# moire_v2_3.net
KiCad netlist of a schematic drawn in EAGLE
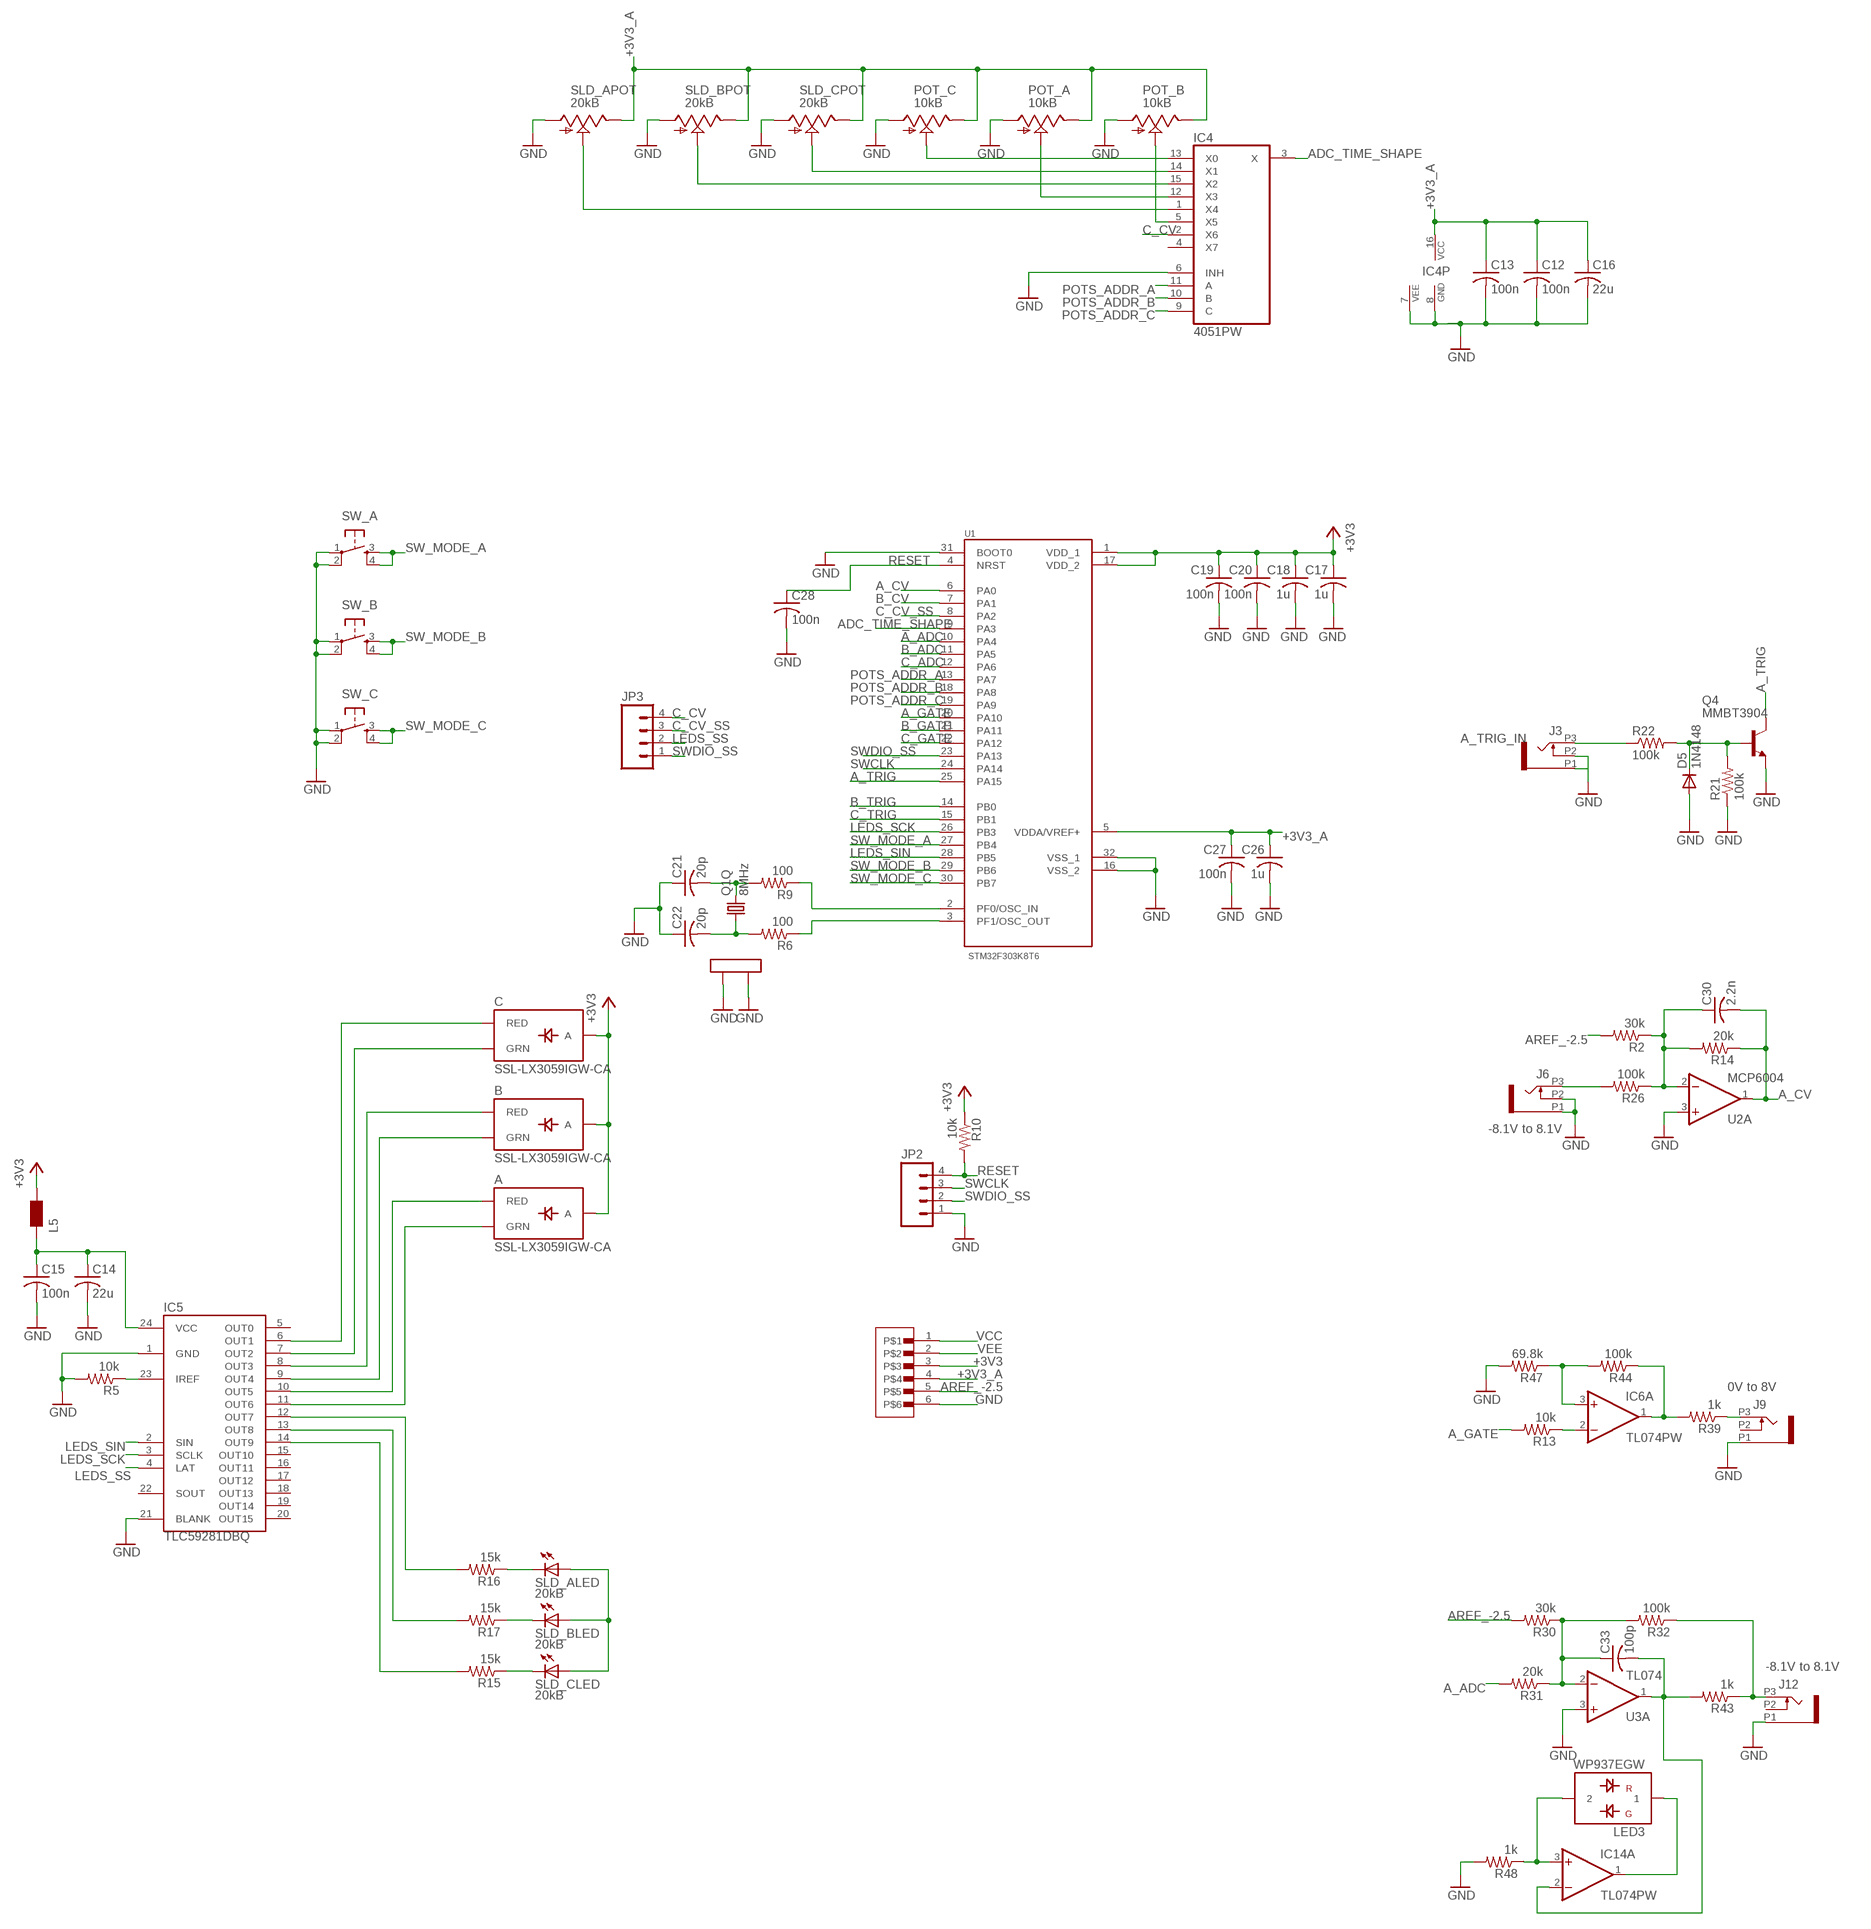
[diagram p0: schematic, sheet 1, part 1 of 2]
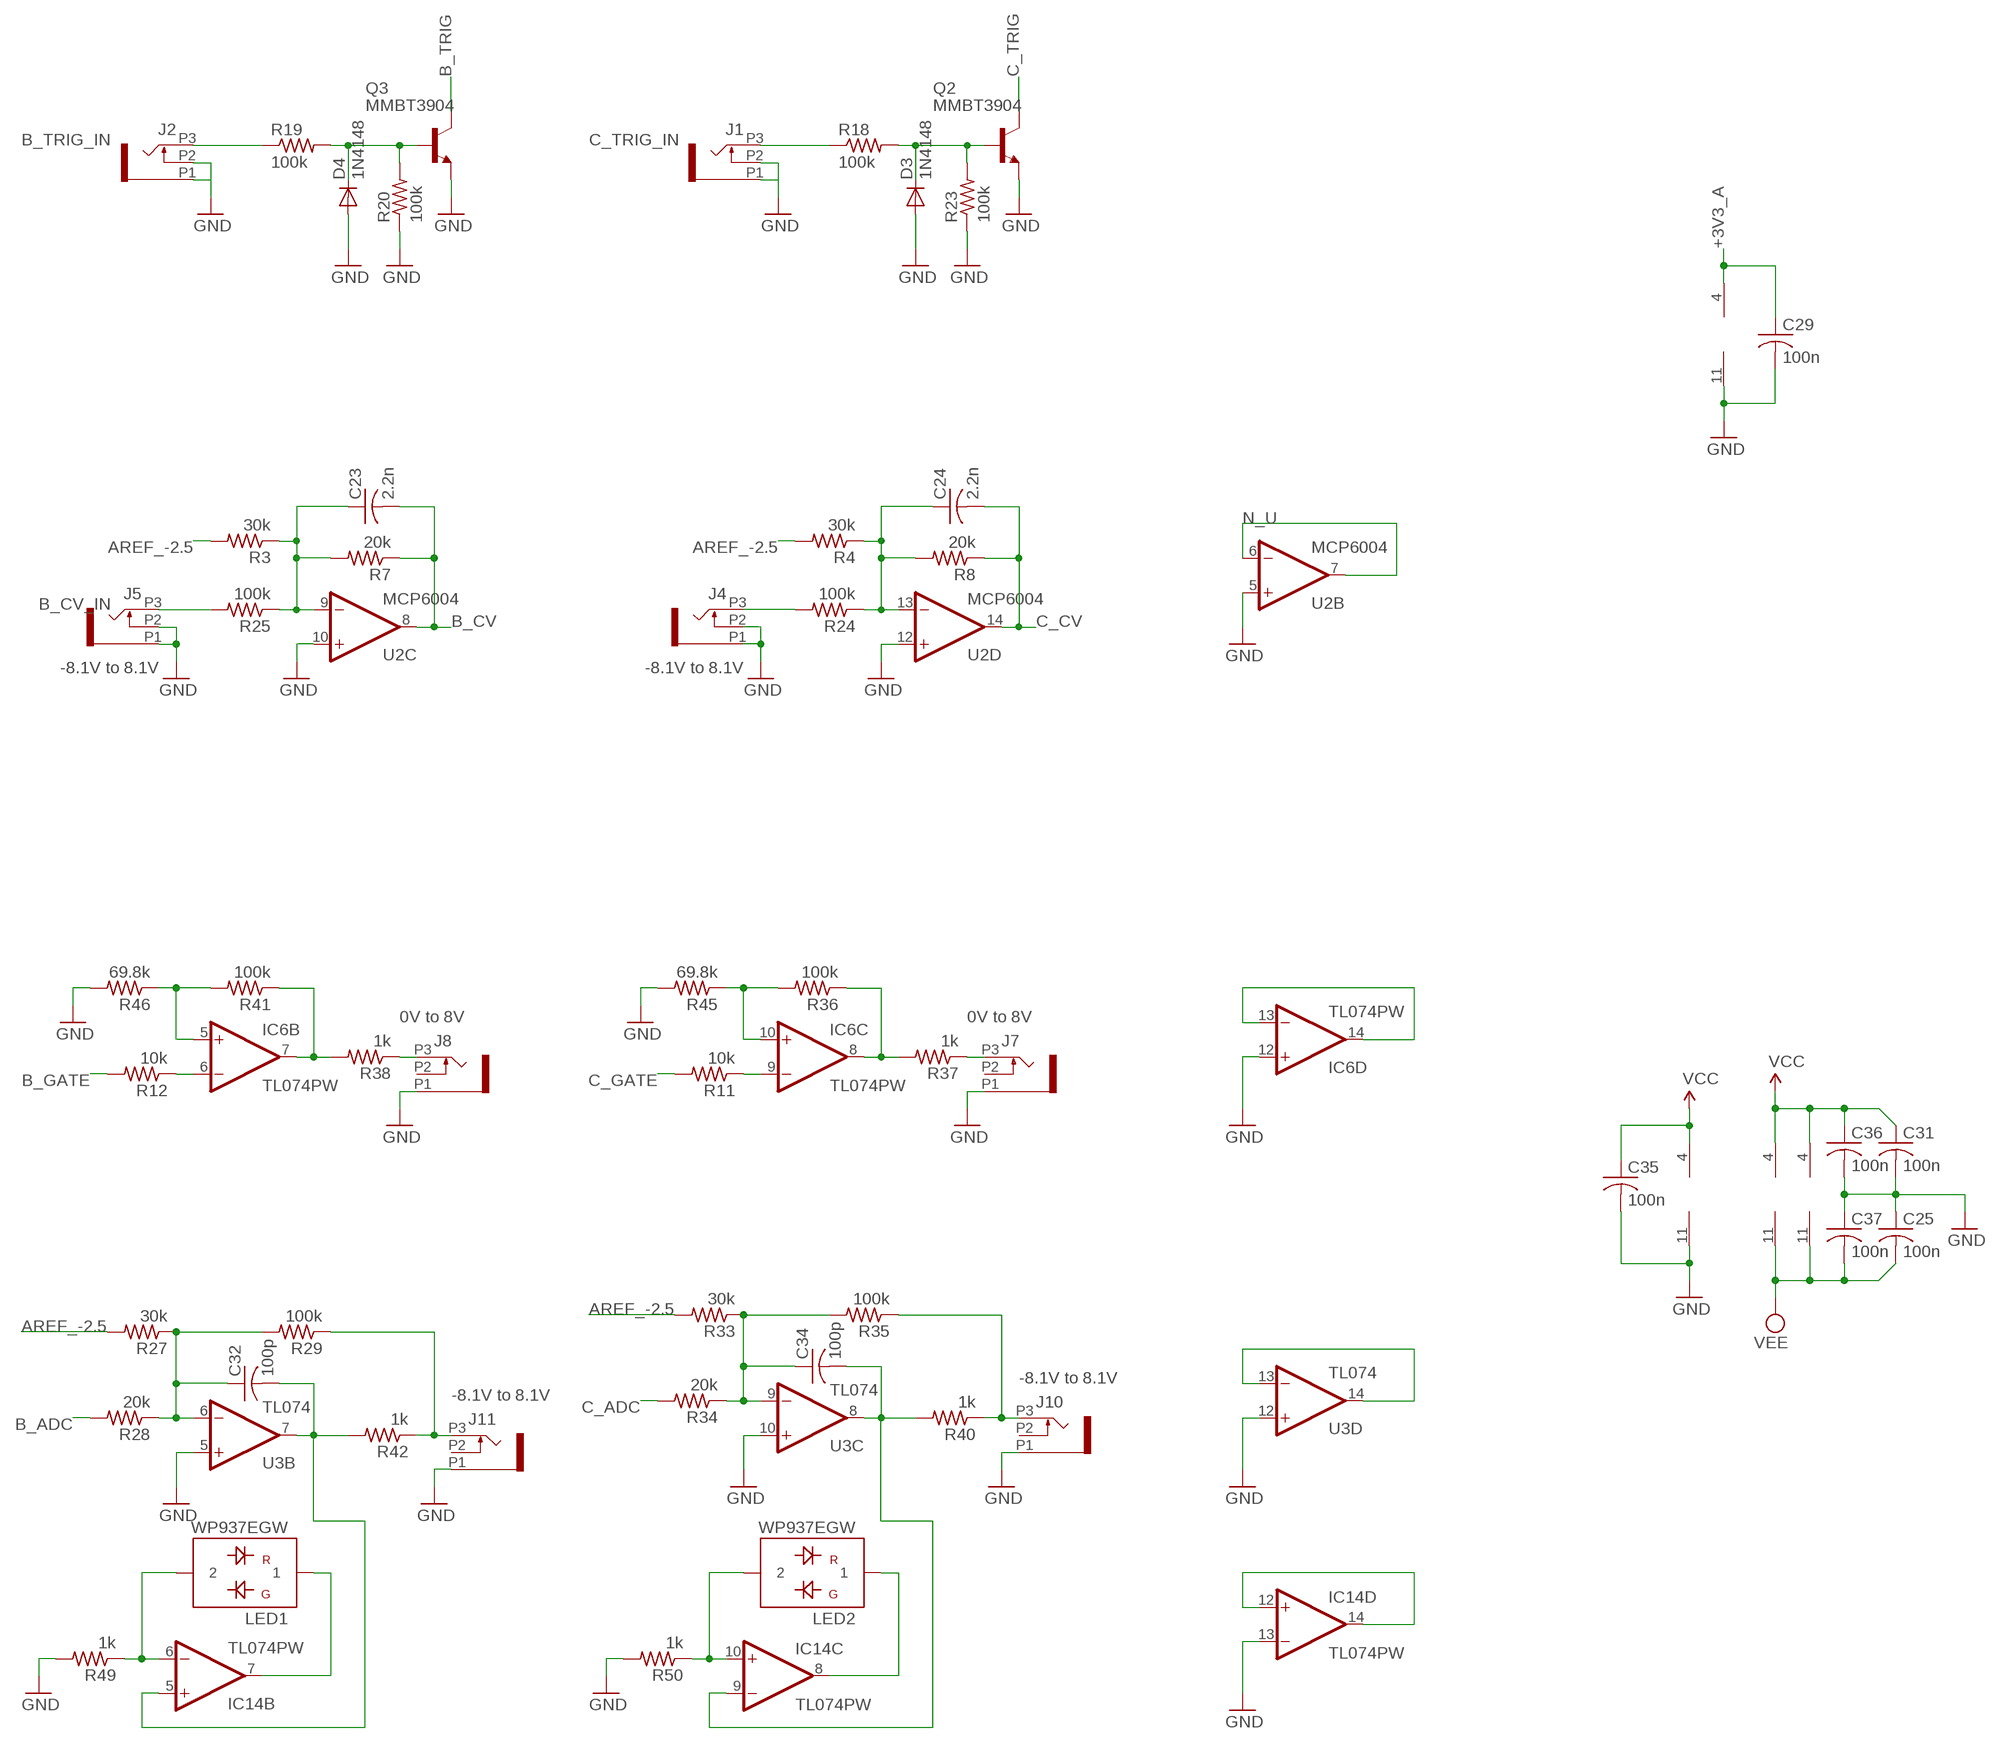
[diagram p1: schematic, sheet 1, part 2 of 2]
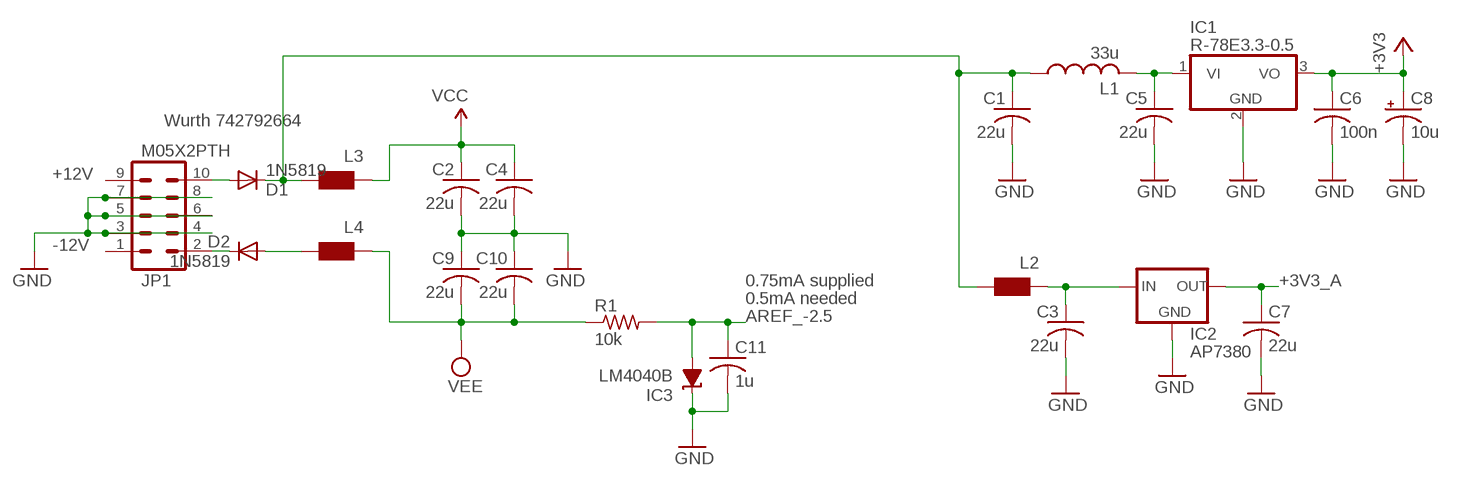
[diagram p2: schematic, sheet 2]

(export (version "E")
  (design (tool "Eeschema 10.0.6"))
  (components
    (comp (ref "A")
      (value "SSL-LX3059IGW-CA")
      (footprint "eagle-import:LED-BICOLOR-THROUGHHOLE-LUMEX")
      (libsource (lib "eagle-import") (part "LED-BICOLOR-THROUGHHOLE-CA"))
    )
    (comp (ref "B")
      (value "SSL-LX3059IGW-CA")
      (footprint "eagle-import:LED-BICOLOR-THROUGHHOLE-LUMEX")
      (libsource (lib "eagle-import") (part "LED-BICOLOR-THROUGHHOLE-CA"))
    )
    (comp (ref "C")
      (value "SSL-LX3059IGW-CA")
      (footprint "eagle-import:LED-BICOLOR-THROUGHHOLE-LUMEX")
      (libsource (lib "eagle-import") (part "LED-BICOLOR-THROUGHHOLE-CA"))
    )
    (comp (ref "C12")
      (value "100n")
      (footprint "eagle-import:RCL_C0603")
      (libsource (lib "eagle-import") (part "RCL_C-USC0603"))
    )
    (comp (ref "C13")
      (value "100n")
      (footprint "eagle-import:RCL_C0603")
      (libsource (lib "eagle-import") (part "RCL_C-USC0603"))
    )
    (comp (ref "C14")
      (value "22u")
      (footprint "eagle-import:RCL_C1206")
      (libsource (lib "eagle-import") (part "RCL_C-USC1206"))
    )
    (comp (ref "C15")
      (value "100n")
      (footprint "eagle-import:RCL_C0603")
      (libsource (lib "eagle-import") (part "RCL_C-USC0603"))
    )
    (comp (ref "C16")
      (value "22u")
      (footprint "eagle-import:RCL_C1206")
      (libsource (lib "eagle-import") (part "RCL_C-USC1206"))
    )
    (comp (ref "C17")
      (value "1u")
      (footprint "eagle-import:RCL_C0603")
      (libsource (lib "eagle-import") (part "RCL_C-USC0603"))
    )
    (comp (ref "C18")
      (value "1u")
      (footprint "eagle-import:RCL_C0603")
      (libsource (lib "eagle-import") (part "RCL_C-USC0603"))
    )
    (comp (ref "C19")
      (value "100n")
      (footprint "eagle-import:RCL_C0603")
      (libsource (lib "eagle-import") (part "RCL_C-USC0603"))
    )
    (comp (ref "C20")
      (value "100n")
      (footprint "eagle-import:RCL_C0603")
      (libsource (lib "eagle-import") (part "RCL_C-USC0603"))
    )
    (comp (ref "C21")
      (value "20p")
      (footprint "eagle-import:RCL_C0603")
      (libsource (lib "eagle-import") (part "RCL_C-USC0603"))
    )
    (comp (ref "C22")
      (value "20p")
      (footprint "eagle-import:RCL_C0603")
      (libsource (lib "eagle-import") (part "RCL_C-USC0603"))
    )
    (comp (ref "C23")
      (value "2.2n")
      (footprint "eagle-import:RCL_C0603")
      (libsource (lib "eagle-import") (part "RCL_C-USC0603"))
    )
    (comp (ref "C24")
      (value "2.2n")
      (footprint "eagle-import:RCL_C0603")
      (libsource (lib "eagle-import") (part "RCL_C-USC0603"))
    )
    (comp (ref "C25")
      (value "100n")
      (footprint "eagle-import:RCL_C0603")
      (libsource (lib "eagle-import") (part "RCL_C-USC0603"))
    )
    (comp (ref "C26")
      (value "1u")
      (footprint "eagle-import:RCL_C0603")
      (libsource (lib "eagle-import") (part "RCL_C-USC0603"))
    )
    (comp (ref "C27")
      (value "100n")
      (footprint "eagle-import:RCL_C0603")
      (libsource (lib "eagle-import") (part "RCL_C-USC0603"))
    )
    (comp (ref "C28")
      (value "100n")
      (footprint "eagle-import:RCL_C0603")
      (libsource (lib "eagle-import") (part "RCL_C-USC0603"))
    )
    (comp (ref "C29")
      (value "100n")
      (footprint "eagle-import:RCL_C0603")
      (libsource (lib "eagle-import") (part "RCL_C-USC0603"))
    )
    (comp (ref "C30")
      (value "2.2n")
      (footprint "eagle-import:RCL_C0603")
      (libsource (lib "eagle-import") (part "RCL_C-USC0603"))
    )
    (comp (ref "C31")
      (value "100n")
      (footprint "eagle-import:RCL_C0603")
      (libsource (lib "eagle-import") (part "RCL_C-USC0603"))
    )
    (comp (ref "C32")
      (value "100p")
      (footprint "eagle-import:RCL_C0603")
      (libsource (lib "eagle-import") (part "RCL_C-USC0603"))
    )
    (comp (ref "C33")
      (value "100p")
      (footprint "eagle-import:RCL_C0603")
      (libsource (lib "eagle-import") (part "RCL_C-USC0603"))
    )
    (comp (ref "C34")
      (value "100p")
      (footprint "eagle-import:RCL_C0603")
      (libsource (lib "eagle-import") (part "RCL_C-USC0603"))
    )
    (comp (ref "C35")
      (value "100n")
      (footprint "eagle-import:RCL_C0603")
      (libsource (lib "eagle-import") (part "RCL_C-USC0603"))
    )
    (comp (ref "C36")
      (value "100n")
      (footprint "eagle-import:RCL_C0603")
      (libsource (lib "eagle-import") (part "RCL_C-USC0603"))
    )
    (comp (ref "C37")
      (value "100n")
      (footprint "eagle-import:RCL_C0603")
      (libsource (lib "eagle-import") (part "RCL_C-USC0603"))
    )
    (comp (ref "D3")
      (value "1N4148")
      (footprint "eagle-import:DIODE_SOD523")
      (libsource (lib "eagle-import") (part "DIODE_DIODE-SOD523"))
    )
    (comp (ref "D4")
      (value "1N4148")
      (footprint "eagle-import:DIODE_SOD523")
      (libsource (lib "eagle-import") (part "DIODE_DIODE-SOD523"))
    )
    (comp (ref "D5")
      (value "1N4148")
      (footprint "eagle-import:DIODE_SOD523")
      (libsource (lib "eagle-import") (part "DIODE_DIODE-SOD523"))
    )
    (comp (ref "IC4")
      (value "4051PW")
      (footprint "eagle-import:TSSOP16_065")
      (libsource (lib "eagle-import") (part "4051PW"))
    )
    (comp (ref "IC5")
      (value "TLC59281DBQ")
      (footprint "eagle-import:TSSOP24_0635")
      (libsource (lib "eagle-import") (part "TLC59281DBQ"))
    )
    (comp (ref "IC6")
      (value "TL074PW")
      (footprint "eagle-import:TSSOP14_065")
      (libsource (lib "eagle-import") (part "og-linear_TL074PW"))
    )
    (comp (ref "IC14")
      (value "TL074PW")
      (footprint "eagle-import:TSSOP14_065")
      (libsource (lib "eagle-import") (part "TL074PW"))
    )
    (comp (ref "J1")
      (value "PJ301_THONKICONN6")
      (footprint "eagle-import:WQP_PJ_301M6")
      (libsource (lib "eagle-import") (part "PJ301_THONKICONN6"))
    )
    (comp (ref "J2")
      (value "PJ301_THONKICONN6")
      (footprint "eagle-import:WQP_PJ_301M6")
      (libsource (lib "eagle-import") (part "PJ301_THONKICONN6"))
    )
    (comp (ref "J3")
      (value "PJ301_THONKICONN6")
      (footprint "eagle-import:WQP_PJ_301M6")
      (libsource (lib "eagle-import") (part "PJ301_THONKICONN6"))
    )
    (comp (ref "J4")
      (value "PJ301_THONKICONN6")
      (footprint "eagle-import:WQP_PJ_301M6")
      (libsource (lib "eagle-import") (part "PJ301_THONKICONN6"))
    )
    (comp (ref "J5")
      (value "PJ301_THONKICONN6")
      (footprint "eagle-import:WQP_PJ_301M6")
      (libsource (lib "eagle-import") (part "PJ301_THONKICONN6"))
    )
    (comp (ref "J6")
      (value "PJ301_THONKICONN6")
      (footprint "eagle-import:WQP_PJ_301M6")
      (libsource (lib "eagle-import") (part "PJ301_THONKICONN6"))
    )
    (comp (ref "J7")
      (value "PJ301_THONKICONN6")
      (footprint "eagle-import:WQP_PJ_301M6")
      (libsource (lib "eagle-import") (part "PJ301_THONKICONN6"))
    )
    (comp (ref "J8")
      (value "PJ301_THONKICONN6")
      (footprint "eagle-import:WQP_PJ_301M6")
      (libsource (lib "eagle-import") (part "PJ301_THONKICONN6"))
    )
    (comp (ref "J9")
      (value "PJ301_THONKICONN6")
      (footprint "eagle-import:WQP_PJ_301M6")
      (libsource (lib "eagle-import") (part "PJ301_THONKICONN6"))
    )
    (comp (ref "J10")
      (value "PJ301_THONKICONN6")
      (footprint "eagle-import:WQP_PJ_301M6")
      (libsource (lib "eagle-import") (part "PJ301_THONKICONN6"))
    )
    (comp (ref "J11")
      (value "PJ301_THONKICONN6")
      (footprint "eagle-import:WQP_PJ_301M6")
      (libsource (lib "eagle-import") (part "PJ301_THONKICONN6"))
    )
    (comp (ref "J12")
      (value "PJ301_THONKICONN6")
      (footprint "eagle-import:WQP_PJ_301M6")
      (libsource (lib "eagle-import") (part "PJ301_THONKICONN6"))
    )
    (comp (ref "JP2")
      (value "M04PTH")
      (footprint "eagle-import:1X04")
      (libsource (lib "eagle-import") (part "M04PTH"))
    )
    (comp (ref "JP3")
      (value "M04PTH")
      (footprint "eagle-import:1X04")
      (libsource (lib "eagle-import") (part "M04PTH"))
    )
    (comp (ref "L5")
      (value "WE-CBF_0603")
      (footprint "eagle-import:0603")
      (libsource (lib "eagle-import") (part "WE-CBF_0603"))
    )
    (comp (ref "LED1")
      (value "WP937EGW")
      (footprint "eagle-import:LED3MM")
      (libsource (lib "eagle-import") (part "LED-BICOLOR-SHARED-THROUGHHOLE"))
    )
    (comp (ref "LED2")
      (value "WP937EGW")
      (footprint "eagle-import:LED3MM")
      (libsource (lib "eagle-import") (part "LED-BICOLOR-SHARED-THROUGHHOLE"))
    )
    (comp (ref "LED3")
      (value "WP937EGW")
      (footprint "eagle-import:LED3MM")
      (libsource (lib "eagle-import") (part "LED-BICOLOR-SHARED-THROUGHHOLE"))
    )
    (comp (ref "POT_A")
      (value "10kB")
      (footprint "eagle-import:ALPS_POT_VERTICAL")
      (libsource (lib "eagle-import") (part "POT_USVERTICAL"))
    )
    (comp (ref "POT_B")
      (value "10kB")
      (footprint "eagle-import:ALPS_POT_VERTICAL")
      (libsource (lib "eagle-import") (part "POT_USVERTICAL"))
    )
    (comp (ref "POT_C")
      (value "10kB")
      (footprint "eagle-import:ALPS_POT_VERTICAL")
      (libsource (lib "eagle-import") (part "POT_USVERTICAL"))
    )
    (comp (ref "Q1")
      (value "8MHz")
      (footprint "eagle-import:CTS406")
      (libsource (lib "eagle-import") (part "CRYSTAL"))
    )
    (comp (ref "Q2")
      (value "MMBT3904")
      (footprint "eagle-import:SOT23-BEC")
      (libsource (lib "eagle-import") (part "-NPN-SOT23-BECMMBT3904LT1"))
    )
    (comp (ref "Q3")
      (value "MMBT3904")
      (footprint "eagle-import:SOT23-BEC")
      (libsource (lib "eagle-import") (part "-NPN-SOT23-BECMMBT3904LT1"))
    )
    (comp (ref "Q4")
      (value "MMBT3904")
      (footprint "eagle-import:SOT23-BEC")
      (libsource (lib "eagle-import") (part "-NPN-SOT23-BECMMBT3904LT1"))
    )
    (comp (ref "R2")
      (value "30k")
      (footprint "eagle-import:RCL_R0603")
      (libsource (lib "eagle-import") (part "RCL_R-US_R0603"))
    )
    (comp (ref "R3")
      (value "30k")
      (footprint "eagle-import:RCL_R0603")
      (libsource (lib "eagle-import") (part "RCL_R-US_R0603"))
    )
    (comp (ref "R4")
      (value "30k")
      (footprint "eagle-import:RCL_R0603")
      (libsource (lib "eagle-import") (part "RCL_R-US_R0603"))
    )
    (comp (ref "R5")
      (value "10k")
      (footprint "eagle-import:RCL_R0603")
      (libsource (lib "eagle-import") (part "RCL_R-US_R0603"))
    )
    (comp (ref "R6")
      (value "100")
      (footprint "eagle-import:RCL_R0603")
      (libsource (lib "eagle-import") (part "RCL_R-US_R0603"))
    )
    (comp (ref "R7")
      (value "20k")
      (footprint "eagle-import:RCL_R0603")
      (libsource (lib "eagle-import") (part "RCL_R-US_R0603"))
    )
    (comp (ref "R8")
      (value "20k")
      (footprint "eagle-import:RCL_R0603")
      (libsource (lib "eagle-import") (part "RCL_R-US_R0603"))
    )
    (comp (ref "R9")
      (value "100")
      (footprint "eagle-import:RCL_R0603")
      (libsource (lib "eagle-import") (part "RCL_R-US_R0603"))
    )
    (comp (ref "R10")
      (value "10k")
      (footprint "eagle-import:RCL_R0603")
      (libsource (lib "eagle-import") (part "RCL_R-US_R0603"))
    )
    (comp (ref "R11")
      (value "10k")
      (footprint "eagle-import:RCL_R0603")
      (libsource (lib "eagle-import") (part "RCL_R-US_R0603"))
    )
    (comp (ref "R12")
      (value "10k")
      (footprint "eagle-import:RCL_R0603")
      (libsource (lib "eagle-import") (part "RCL_R-US_R0603"))
    )
    (comp (ref "R13")
      (value "10k")
      (footprint "eagle-import:RCL_R0603")
      (libsource (lib "eagle-import") (part "RCL_R-US_R0603"))
    )
    (comp (ref "R14")
      (value "20k")
      (footprint "eagle-import:RCL_R0603")
      (libsource (lib "eagle-import") (part "RCL_R-US_R0603"))
    )
    (comp (ref "R15")
      (value "15k")
      (footprint "eagle-import:RCL_R0603")
      (libsource (lib "eagle-import") (part "RCL_R-US_R0603"))
    )
    (comp (ref "R16")
      (value "15k")
      (footprint "eagle-import:RCL_R0603")
      (libsource (lib "eagle-import") (part "RCL_R-US_R0603"))
    )
    (comp (ref "R17")
      (value "15k")
      (footprint "eagle-import:RCL_R0603")
      (libsource (lib "eagle-import") (part "RCL_R-US_R0603"))
    )
    (comp (ref "R18")
      (value "100k")
      (footprint "eagle-import:RCL_R0603")
      (libsource (lib "eagle-import") (part "RCL_R-US_R0603"))
    )
    (comp (ref "R19")
      (value "100k")
      (footprint "eagle-import:RCL_R0603")
      (libsource (lib "eagle-import") (part "RCL_R-US_R0603"))
    )
    (comp (ref "R20")
      (value "100k")
      (footprint "eagle-import:RCL_R0603")
      (libsource (lib "eagle-import") (part "RCL_R-US_R0603"))
    )
    (comp (ref "R21")
      (value "100k")
      (footprint "eagle-import:RCL_R0603")
      (libsource (lib "eagle-import") (part "RCL_R-US_R0603"))
    )
    (comp (ref "R22")
      (value "100k")
      (footprint "eagle-import:RCL_R0603")
      (libsource (lib "eagle-import") (part "RCL_R-US_R0603"))
    )
    (comp (ref "R23")
      (value "100k")
      (footprint "eagle-import:RCL_R0603")
      (libsource (lib "eagle-import") (part "RCL_R-US_R0603"))
    )
    (comp (ref "R24")
      (value "100k")
      (footprint "eagle-import:RCL_R0603")
      (libsource (lib "eagle-import") (part "RCL_R-US_R0603"))
    )
    (comp (ref "R25")
      (value "100k")
      (footprint "eagle-import:RCL_R0603")
      (libsource (lib "eagle-import") (part "RCL_R-US_R0603"))
    )
    (comp (ref "R26")
      (value "100k")
      (footprint "eagle-import:RCL_R0603")
      (libsource (lib "eagle-import") (part "RCL_R-US_R0603"))
    )
    (comp (ref "R27")
      (value "30k")
      (footprint "eagle-import:RCL_R0603")
      (libsource (lib "eagle-import") (part "RCL_R-US_R0603"))
    )
    (comp (ref "R28")
      (value "20k")
      (footprint "eagle-import:RCL_R0603")
      (libsource (lib "eagle-import") (part "RCL_R-US_R0603"))
    )
    (comp (ref "R29")
      (value "100k")
      (footprint "eagle-import:RCL_R0603")
      (libsource (lib "eagle-import") (part "RCL_R-US_R0603"))
    )
    (comp (ref "R30")
      (value "30k")
      (footprint "eagle-import:RCL_R0603")
      (libsource (lib "eagle-import") (part "RCL_R-US_R0603"))
    )
    (comp (ref "R31")
      (value "20k")
      (footprint "eagle-import:RCL_R0603")
      (libsource (lib "eagle-import") (part "RCL_R-US_R0603"))
    )
    (comp (ref "R32")
      (value "100k")
      (footprint "eagle-import:RCL_R0603")
      (libsource (lib "eagle-import") (part "RCL_R-US_R0603"))
    )
    (comp (ref "R33")
      (value "30k")
      (footprint "eagle-import:RCL_R0603")
      (libsource (lib "eagle-import") (part "RCL_R-US_R0603"))
    )
    (comp (ref "R34")
      (value "20k")
      (footprint "eagle-import:RCL_R0603")
      (libsource (lib "eagle-import") (part "RCL_R-US_R0603"))
    )
    (comp (ref "R35")
      (value "100k")
      (footprint "eagle-import:RCL_R0603")
      (libsource (lib "eagle-import") (part "RCL_R-US_R0603"))
    )
    (comp (ref "R36")
      (value "100k")
      (footprint "eagle-import:RCL_R0603")
      (libsource (lib "eagle-import") (part "RCL_R-US_R0603"))
    )
    (comp (ref "R37")
      (value "1k")
      (footprint "eagle-import:RCL_R0603")
      (libsource (lib "eagle-import") (part "RCL_R-US_R0603"))
    )
    (comp (ref "R38")
      (value "1k")
      (footprint "eagle-import:RCL_R0603")
      (libsource (lib "eagle-import") (part "RCL_R-US_R0603"))
    )
    (comp (ref "R39")
      (value "1k")
      (footprint "eagle-import:RCL_R0603")
      (libsource (lib "eagle-import") (part "RCL_R-US_R0603"))
    )
    (comp (ref "R40")
      (value "1k")
      (footprint "eagle-import:RCL_R0603")
      (libsource (lib "eagle-import") (part "RCL_R-US_R0603"))
    )
    (comp (ref "R41")
      (value "100k")
      (footprint "eagle-import:RCL_R0603")
      (libsource (lib "eagle-import") (part "RCL_R-US_R0603"))
    )
    (comp (ref "R42")
      (value "1k")
      (footprint "eagle-import:RCL_R0603")
      (libsource (lib "eagle-import") (part "RCL_R-US_R0603"))
    )
    (comp (ref "R43")
      (value "1k")
      (footprint "eagle-import:RCL_R0603")
      (libsource (lib "eagle-import") (part "RCL_R-US_R0603"))
    )
    (comp (ref "R44")
      (value "100k")
      (footprint "eagle-import:RCL_R0603")
      (libsource (lib "eagle-import") (part "RCL_R-US_R0603"))
    )
    (comp (ref "R45")
      (value "69.8k")
      (footprint "eagle-import:RCL_R0603")
      (libsource (lib "eagle-import") (part "RCL_R-US_R0603"))
    )
    (comp (ref "R46")
      (value "69.8k")
      (footprint "eagle-import:RCL_R0603")
      (libsource (lib "eagle-import") (part "RCL_R-US_R0603"))
    )
    (comp (ref "R47")
      (value "69.8k")
      (footprint "eagle-import:RCL_R0603")
      (libsource (lib "eagle-import") (part "RCL_R-US_R0603"))
    )
    (comp (ref "R48")
      (value "1k")
      (footprint "eagle-import:RCL_R0603")
      (libsource (lib "eagle-import") (part "RCL_R-US_R0603"))
    )
    (comp (ref "R49")
      (value "1k")
      (footprint "eagle-import:RCL_R0603")
      (libsource (lib "eagle-import") (part "RCL_R-US_R0603"))
    )
    (comp (ref "R50")
      (value "1k")
      (footprint "eagle-import:RCL_R0603")
      (libsource (lib "eagle-import") (part "RCL_R-US_R0603"))
    )
    (comp (ref "SLD_A")
      (value "20kB")
      (footprint "eagle-import:BOURNS_SLIDER")
      (libsource (lib "eagle-import") (part "BOURNS_SLIDER"))
    )
    (comp (ref "SLD_B")
      (value "20kB")
      (footprint "eagle-import:BOURNS_SLIDER")
      (libsource (lib "eagle-import") (part "BOURNS_SLIDER"))
    )
    (comp (ref "SLD_C")
      (value "20kB")
      (footprint "eagle-import:BOURNS_SLIDER")
      (libsource (lib "eagle-import") (part "BOURNS_SLIDER"))
    )
    (comp (ref "SW_A")
      (value "TAC_SWITCHPTH")
      (footprint "eagle-import:TACTILE-PTH")
      (libsource (lib "eagle-import") (part "TAC_SWITCHPTH"))
    )
    (comp (ref "SW_B")
      (value "TAC_SWITCHPTH")
      (footprint "eagle-import:TACTILE-PTH")
      (libsource (lib "eagle-import") (part "TAC_SWITCHPTH"))
    )
    (comp (ref "SW_C")
      (value "TAC_SWITCHPTH")
      (footprint "eagle-import:TACTILE-PTH")
      (libsource (lib "eagle-import") (part "TAC_SWITCHPTH"))
    )
    (comp (ref "U$1")
      (value "1X6-SMD-TESTPAD")
      (footprint "eagle-import:6X1-SMD-TESTPAD")
      (libsource (lib "eagle-import") (part "1X6-SMD-TESTPAD"))
    )
    (comp (ref "U1")
      (value "STM32F303K8T6")
      (footprint "eagle-import:QFP80P900X900X160-32N")
      (fields (field (name "MF") "STMicroelectronics"))
      (libsource (lib "eagle-import") (part "STM32F303K8T6"))
    )
    (comp (ref "U2")
      (value "MCP6004")
      (footprint "eagle-import:SO14")
      (libsource (lib "eagle-import") (part "MCP6004_SMD"))
    )
    (comp (ref "U3")
      (value "TL074")
      (footprint "eagle-import:SO14")
      (libsource (lib "eagle-import") (part "TL074_SMD"))
    )
    (comp (ref "C1")
      (value "22u")
      (footprint "eagle-import:RCL_C1206")
      (libsource (lib "eagle-import") (part "RCL_C-USC1206"))
    )
    (comp (ref "C2")
      (value "22u")
      (footprint "eagle-import:RCL_C1206")
      (libsource (lib "eagle-import") (part "RCL_C-USC1206"))
    )
    (comp (ref "C3")
      (value "22u")
      (footprint "eagle-import:RCL_C1206")
      (libsource (lib "eagle-import") (part "RCL_C-USC1206"))
    )
    (comp (ref "C4")
      (value "22u")
      (footprint "eagle-import:RCL_C1206")
      (libsource (lib "eagle-import") (part "RCL_C-USC1206"))
    )
    (comp (ref "C5")
      (value "22u")
      (footprint "eagle-import:RCL_C1206")
      (libsource (lib "eagle-import") (part "RCL_C-USC1206"))
    )
    (comp (ref "C6")
      (value "100n")
      (footprint "eagle-import:RCL_C0603")
      (libsource (lib "eagle-import") (part "RCL_C-USC0603"))
    )
    (comp (ref "C7")
      (value "22u")
      (footprint "eagle-import:RCL_C1206")
      (libsource (lib "eagle-import") (part "RCL_C-USC1206"))
    )
    (comp (ref "C8")
      (value "10u")
      (footprint "eagle-import:RCL_PANASONIC_A")
      (libsource (lib "eagle-import") (part "RCL_CPOL-USA"))
    )
    (comp (ref "C9")
      (value "22u")
      (footprint "eagle-import:RCL_C1206")
      (libsource (lib "eagle-import") (part "RCL_C-USC1206"))
    )
    (comp (ref "C10")
      (value "22u")
      (footprint "eagle-import:RCL_C1206")
      (libsource (lib "eagle-import") (part "RCL_C-USC1206"))
    )
    (comp (ref "C11")
      (value "1u")
      (footprint "eagle-import:RCL_C0603")
      (libsource (lib "eagle-import") (part "RCL_C-USC0603"))
    )
    (comp (ref "D1")
      (value "1N5819")
      (footprint "eagle-import:DIODE_SOD123")
      (libsource (lib "eagle-import") (part "DIODE_DIODE-SOD123"))
    )
    (comp (ref "D2")
      (value "1N5819")
      (footprint "eagle-import:DIODE_SOD123")
      (libsource (lib "eagle-import") (part "DIODE_DIODE-SOD123"))
    )
    (comp (ref "IC1")
      (value "R-78E3.3-0.5")
      (footprint "eagle-import:WE78")
      (libsource (lib "eagle-import") (part "WE173950378"))
    )
    (comp (ref "IC2")
      (value "AP7380")
      (footprint "eagle-import:SOT89")
      (libsource (lib "eagle-import") (part "AP7380"))
    )
    (comp (ref "IC3")
      (value "LM4040B")
      (footprint "eagle-import:DBZ_R-PDSO-G3")
      (libsource (lib "eagle-import") (part "LM4041DBZB12"))
    )
    (comp (ref "JP1")
      (value "M05X2PTH")
      (footprint "eagle-import:2X5-PTH")
      (libsource (lib "eagle-import") (part "M05X2PTH"))
    )
    (comp (ref "L1")
      (value "33u")
      (footprint "eagle-import:L2012C")
      (libsource (lib "eagle-import") (part "L-USL2012C"))
    )
    (comp (ref "L2")
      (value "WE-CBF_0603")
      (footprint "eagle-import:0603")
      (libsource (lib "eagle-import") (part "WE-CBF_0603"))
    )
    (comp (ref "L3")
      (value "WE-CBF_0603")
      (footprint "eagle-import:0603")
      (libsource (lib "eagle-import") (part "WE-CBF_0603"))
    )
    (comp (ref "L4")
      (value "WE-CBF_0603")
      (footprint "eagle-import:0603")
      (libsource (lib "eagle-import") (part "WE-CBF_0603"))
    )
    (comp (ref "R1")
      (value "10k")
      (footprint "eagle-import:RCL_R0603")
      (libsource (lib "eagle-import") (part "RCL_R-US_R0603"))
    )
  )
  (nets
    (net (code "1") (name "+3V3") (class "Default")
      (node (ref "A") (pin "A") (pinfunction "A_A") (pintype "bidirectional"))
      (node (ref "B") (pin "A") (pinfunction "A_A") (pintype "bidirectional"))
      (node (ref "C") (pin "A") (pinfunction "A_A") (pintype "bidirectional"))
      (node (ref "C17") (pin "1") (pinfunction "1_1") (pintype "passive"))
      (node (ref "C18") (pin "1") (pinfunction "1_1") (pintype "passive"))
      (node (ref "C19") (pin "1") (pinfunction "1_1") (pintype "passive"))
      (node (ref "C20") (pin "1") (pinfunction "1_1") (pintype "passive"))
      (node (ref "C6") (pin "1") (pinfunction "1_1") (pintype "passive"))
      (node (ref "C8") (pin "+") (pinfunction "+_+") (pintype "passive"))
      (node (ref "IC1") (pin "3") (pinfunction "VO_3") (pintype "passive"))
      (node (ref "L5") (pin "2") (pinfunction "2_2") (pintype "passive"))
      (node (ref "R10") (pin "1") (pinfunction "1_1") (pintype "passive"))
      (node (ref "U$1") (pin "3") (pinfunction "P$3_3") (pintype "bidirectional"))
      (node (ref "U1") (pin "1") (pinfunction "VDD_1_1") (pintype "power_in"))
      (node (ref "U1") (pin "17") (pinfunction "VDD_2_17") (pintype "power_in"))
    )
    (net (code "2") (name "+3V3_A") (class "Default")
      (node (ref "C12") (pin "1") (pinfunction "1_1") (pintype "passive"))
      (node (ref "C13") (pin "1") (pinfunction "1_1") (pintype "passive"))
      (node (ref "C16") (pin "1") (pinfunction "1_1") (pintype "passive"))
      (node (ref "C26") (pin "1") (pinfunction "1_1") (pintype "passive"))
      (node (ref "C27") (pin "1") (pinfunction "1_1") (pintype "passive"))
      (node (ref "C29") (pin "1") (pinfunction "1_1") (pintype "passive"))
      (node (ref "C7") (pin "1") (pinfunction "1_1") (pintype "passive"))
      (node (ref "IC2") (pin "3") (pinfunction "OUT_3") (pintype "passive"))
      (node (ref "IC4") (pin "16") (pinfunction "VCC_16") (pintype "power_in"))
      (node (ref "POT_A") (pin "P$1") (pinfunction "E_P$1") (pintype "passive"))
      (node (ref "POT_B") (pin "P$1") (pinfunction "E_P$1") (pintype "passive"))
      (node (ref "POT_C") (pin "P$1") (pinfunction "E_P$1") (pintype "passive"))
      (node (ref "SLD_A") (pin "3") (pinfunction "E_3") (pintype "passive"))
      (node (ref "SLD_B") (pin "3") (pinfunction "E_3") (pintype "passive"))
      (node (ref "SLD_C") (pin "3") (pinfunction "E_3") (pintype "passive"))
      (node (ref "U$1") (pin "4") (pinfunction "P$4_4") (pintype "bidirectional"))
      (node (ref "U1") (pin "5") (pinfunction "VDDA/VREF+_5") (pintype "power_in"))
      (node (ref "U2") (pin "4") (pinfunction "V+_4") (pintype "power_in"))
    )
    (net (code "3") (name "+12V") (class "Default")
      (node (ref "D1") (pin "A") (pinfunction "A_A") (pintype "passive"))
      (node (ref "JP1") (pin "10") (pinfunction "10_10") (pintype "passive"))
      (node (ref "JP1") (pin "9") (pinfunction "9_9") (pintype "passive"))
    )
    (net (code "4") (name "-12V") (class "Default")
      (node (ref "D2") (pin "C") (pinfunction "C_C") (pintype "passive"))
      (node (ref "JP1") (pin "1") (pinfunction "1_1") (pintype "passive"))
      (node (ref "JP1") (pin "2") (pinfunction "2_2") (pintype "passive"))
    )
    (net (code "5") (name "ADC_TIME_SHAPE") (class "Default")
      (node (ref "IC4") (pin "3") (pinfunction "X_3") (pintype "bidirectional"))
      (node (ref "U1") (pin "9") (pinfunction "PA3_9") (pintype "bidirectional"))
    )
    (net (code "6") (name "AREF_-2.5") (class "Default")
      (node (ref "C11") (pin "1") (pinfunction "1_1") (pintype "passive"))
      (node (ref "IC3") (pin "2") (pinfunction "A_2") (pintype "passive"))
      (node (ref "R1") (pin "2") (pinfunction "2_2") (pintype "passive"))
      (node (ref "R2") (pin "2") (pinfunction "2_2") (pintype "passive"))
      (node (ref "R27") (pin "2") (pinfunction "2_2") (pintype "passive"))
      (node (ref "R3") (pin "2") (pinfunction "2_2") (pintype "passive"))
      (node (ref "R30") (pin "2") (pinfunction "2_2") (pintype "passive"))
      (node (ref "R33") (pin "2") (pinfunction "2_2") (pintype "passive"))
      (node (ref "R4") (pin "2") (pinfunction "2_2") (pintype "passive"))
      (node (ref "U$1") (pin "5") (pinfunction "P$5_5") (pintype "bidirectional"))
    )
    (net (code "7") (name "A_ADC") (class "Default")
      (node (ref "R31") (pin "2") (pinfunction "2_2") (pintype "passive"))
      (node (ref "U1") (pin "10") (pinfunction "PA4_10") (pintype "bidirectional"))
    )
    (net (code "8") (name "A_CV") (class "Default")
      (node (ref "C30") (pin "2") (pinfunction "2_2") (pintype "passive"))
      (node (ref "R14") (pin "1") (pinfunction "1_1") (pintype "passive"))
      (node (ref "U1") (pin "6") (pinfunction "PA0_6") (pintype "bidirectional"))
      (node (ref "U2") (pin "1") (pinfunction "OUT_1") (pintype "output"))
    )
    (net (code "9") (name "A_GATE") (class "Default")
      (node (ref "R13") (pin "2") (pinfunction "2_2") (pintype "passive"))
      (node (ref "U1") (pin "20") (pinfunction "PA10_20") (pintype "bidirectional"))
    )
    (net (code "10") (name "A_TRIG") (class "Default")
      (node (ref "Q4") (pin "C") (pinfunction "C_C") (pintype "passive"))
      (node (ref "U1") (pin "25") (pinfunction "PA15_25") (pintype "bidirectional"))
    )
    (net (code "11") (name "A_TRIG_IN") (class "Default")
      (node (ref "J3") (pin "P3") (pinfunction "3_P3") (pintype "passive"))
      (node (ref "R22") (pin "1") (pinfunction "1_1") (pintype "passive"))
    )
    (net (code "12") (name "B_ADC") (class "Default")
      (node (ref "R28") (pin "2") (pinfunction "2_2") (pintype "passive"))
      (node (ref "U1") (pin "11") (pinfunction "PA5_11") (pintype "bidirectional"))
    )
    (net (code "13") (name "B_CV") (class "Default")
      (node (ref "C23") (pin "2") (pinfunction "2_2") (pintype "passive"))
      (node (ref "R7") (pin "1") (pinfunction "1_1") (pintype "passive"))
      (node (ref "U1") (pin "7") (pinfunction "PA1_7") (pintype "bidirectional"))
      (node (ref "U2") (pin "8") (pinfunction "OUT_8") (pintype "output"))
    )
    (net (code "14") (name "B_CV_IN") (class "Default")
      (node (ref "J5") (pin "P3") (pinfunction "3_P3") (pintype "passive"))
      (node (ref "R25") (pin "2") (pinfunction "2_2") (pintype "passive"))
    )
    (net (code "15") (name "B_GATE") (class "Default")
      (node (ref "R12") (pin "2") (pinfunction "2_2") (pintype "passive"))
      (node (ref "U1") (pin "21") (pinfunction "PA11_21") (pintype "bidirectional"))
    )
    (net (code "16") (name "B_TRIG") (class "Default")
      (node (ref "Q3") (pin "C") (pinfunction "C_C") (pintype "passive"))
      (node (ref "U1") (pin "14") (pinfunction "PB0_14") (pintype "bidirectional"))
    )
    (net (code "17") (name "B_TRIG_IN") (class "Default")
      (node (ref "J2") (pin "P3") (pinfunction "3_P3") (pintype "passive"))
      (node (ref "R19") (pin "1") (pinfunction "1_1") (pintype "passive"))
    )
    (net (code "18") (name "C_ADC") (class "Default")
      (node (ref "R34") (pin "2") (pinfunction "2_2") (pintype "passive"))
      (node (ref "U1") (pin "12") (pinfunction "PA6_12") (pintype "bidirectional"))
    )
    (net (code "19") (name "C_CV") (class "Default")
      (node (ref "C24") (pin "2") (pinfunction "2_2") (pintype "passive"))
      (node (ref "IC4") (pin "2") (pinfunction "X6_2") (pintype "bidirectional"))
      (node (ref "JP3") (pin "4") (pinfunction "4_4") (pintype "passive"))
      (node (ref "R8") (pin "1") (pinfunction "1_1") (pintype "passive"))
      (node (ref "U2") (pin "14") (pinfunction "OUT_14") (pintype "output"))
    )
    (net (code "20") (name "C_CV_SS") (class "Default")
      (node (ref "JP3") (pin "3") (pinfunction "3_3") (pintype "passive"))
      (node (ref "U1") (pin "8") (pinfunction "PA2_8") (pintype "bidirectional"))
    )
    (net (code "21") (name "C_GATE") (class "Default")
      (node (ref "R11") (pin "2") (pinfunction "2_2") (pintype "passive"))
      (node (ref "U1") (pin "22") (pinfunction "PA12_22") (pintype "bidirectional"))
    )
    (net (code "22") (name "C_TRIG") (class "Default")
      (node (ref "Q2") (pin "C") (pinfunction "C_C") (pintype "passive"))
      (node (ref "U1") (pin "15") (pinfunction "PB1_15") (pintype "bidirectional"))
    )
    (net (code "23") (name "C_TRIG_IN") (class "Default")
      (node (ref "J1") (pin "P3") (pinfunction "3_P3") (pintype "passive"))
      (node (ref "R18") (pin "1") (pinfunction "1_1") (pintype "passive"))
    )
    (net (code "24") (name "GND") (class "Default")
      (node (ref "C1") (pin "2") (pinfunction "2_2") (pintype "passive"))
      (node (ref "C10") (pin "1") (pinfunction "1_1") (pintype "passive"))
      (node (ref "C11") (pin "2") (pinfunction "2_2") (pintype "passive"))
      (node (ref "C12") (pin "2") (pinfunction "2_2") (pintype "passive"))
      (node (ref "C13") (pin "2") (pinfunction "2_2") (pintype "passive"))
      (node (ref "C14") (pin "2") (pinfunction "2_2") (pintype "passive"))
      (node (ref "C15") (pin "2") (pinfunction "2_2") (pintype "passive"))
      (node (ref "C16") (pin "2") (pinfunction "2_2") (pintype "passive"))
      (node (ref "C17") (pin "2") (pinfunction "2_2") (pintype "passive"))
      (node (ref "C18") (pin "2") (pinfunction "2_2") (pintype "passive"))
      (node (ref "C19") (pin "2") (pinfunction "2_2") (pintype "passive"))
      (node (ref "C2") (pin "2") (pinfunction "2_2") (pintype "passive"))
      (node (ref "C20") (pin "2") (pinfunction "2_2") (pintype "passive"))
      (node (ref "C21") (pin "1") (pinfunction "1_1") (pintype "passive"))
      (node (ref "C22") (pin "1") (pinfunction "1_1") (pintype "passive"))
      (node (ref "C25") (pin "1") (pinfunction "1_1") (pintype "passive"))
      (node (ref "C26") (pin "2") (pinfunction "2_2") (pintype "passive"))
      (node (ref "C27") (pin "2") (pinfunction "2_2") (pintype "passive"))
      (node (ref "C28") (pin "2") (pinfunction "2_2") (pintype "passive"))
      (node (ref "C29") (pin "2") (pinfunction "2_2") (pintype "passive"))
      (node (ref "C3") (pin "2") (pinfunction "2_2") (pintype "passive"))
      (node (ref "C31") (pin "2") (pinfunction "2_2") (pintype "passive"))
      (node (ref "C35") (pin "2") (pinfunction "2_2") (pintype "passive"))
      (node (ref "C36") (pin "2") (pinfunction "2_2") (pintype "passive"))
      (node (ref "C37") (pin "1") (pinfunction "1_1") (pintype "passive"))
      (node (ref "C4") (pin "2") (pinfunction "2_2") (pintype "passive"))
      (node (ref "C5") (pin "2") (pinfunction "2_2") (pintype "passive"))
      (node (ref "C6") (pin "2") (pinfunction "2_2") (pintype "passive"))
      (node (ref "C7") (pin "2") (pinfunction "2_2") (pintype "passive"))
      (node (ref "C8") (pin "-") (pinfunction "-_-") (pintype "passive"))
      (node (ref "C9") (pin "1") (pinfunction "1_1") (pintype "passive"))
      (node (ref "D3") (pin "A") (pinfunction "A_A") (pintype "passive"))
      (node (ref "D4") (pin "A") (pinfunction "A_A") (pintype "passive"))
      (node (ref "D5") (pin "A") (pinfunction "A_A") (pintype "passive"))
      (node (ref "IC1") (pin "2") (pinfunction "GND_2") (pintype "passive"))
      (node (ref "IC14") (pin "13") (pinfunction "-IN_13") (pintype "input"))
      (node (ref "IC2") (pin "1") (pinfunction "GND_1") (pintype "input"))
      (node (ref "IC3") (pin "1") (pinfunction "C_1") (pintype "passive"))
      (node (ref "IC4") (pin "6") (pinfunction "INH_6") (pintype "input"))
      (node (ref "IC4") (pin "7") (pinfunction "VEE_7") (pintype "power_in"))
      (node (ref "IC4") (pin "8") (pinfunction "GND_8") (pintype "power_in"))
      (node (ref "IC5") (pin "1") (pinfunction "GND_1") (pintype "bidirectional"))
      (node (ref "IC5") (pin "21") (pinfunction "BLANK_21") (pintype "bidirectional"))
      (node (ref "IC6") (pin "11") (pinfunction "V-_11") (pintype "power_in"))
      (node (ref "IC6") (pin "12") (pinfunction "+IN_12") (pintype "input"))
      (node (ref "J1") (pin "P1") (pinfunction "1_P1") (pintype "passive"))
      (node (ref "J1") (pin "P2") (pinfunction "2_P2") (pintype "passive"))
      (node (ref "J10") (pin "P1") (pinfunction "1_P1") (pintype "passive"))
      (node (ref "J11") (pin "P1") (pinfunction "1_P1") (pintype "passive"))
      (node (ref "J12") (pin "P1") (pinfunction "1_P1") (pintype "passive"))
      (node (ref "J2") (pin "P1") (pinfunction "1_P1") (pintype "passive"))
      (node (ref "J2") (pin "P2") (pinfunction "2_P2") (pintype "passive"))
      (node (ref "J3") (pin "P1") (pinfunction "1_P1") (pintype "passive"))
      (node (ref "J3") (pin "P2") (pinfunction "2_P2") (pintype "passive"))
      (node (ref "J4") (pin "P1") (pinfunction "1_P1") (pintype "passive"))
      (node (ref "J4") (pin "P2") (pinfunction "2_P2") (pintype "passive"))
      (node (ref "J5") (pin "P1") (pinfunction "1_P1") (pintype "passive"))
      (node (ref "J5") (pin "P2") (pinfunction "2_P2") (pintype "passive"))
      (node (ref "J6") (pin "P1") (pinfunction "1_P1") (pintype "passive"))
      (node (ref "J6") (pin "P2") (pinfunction "2_P2") (pintype "passive"))
      (node (ref "J7") (pin "P1") (pinfunction "1_P1") (pintype "passive"))
      (node (ref "J8") (pin "P1") (pinfunction "1_P1") (pintype "passive"))
      (node (ref "J9") (pin "P1") (pinfunction "1_P1") (pintype "passive"))
      (node (ref "JP1") (pin "3") (pinfunction "3_3") (pintype "passive"))
      (node (ref "JP1") (pin "4") (pinfunction "4_4") (pintype "passive"))
      (node (ref "JP1") (pin "5") (pinfunction "5_5") (pintype "passive"))
      (node (ref "JP1") (pin "6") (pinfunction "6_6") (pintype "passive"))
      (node (ref "JP1") (pin "7") (pinfunction "7_7") (pintype "passive"))
      (node (ref "JP1") (pin "8") (pinfunction "8_8") (pintype "passive"))
      (node (ref "JP2") (pin "1") (pinfunction "1_1") (pintype "passive"))
      (node (ref "POT_A") (pin "P$3") (pinfunction "A_P$3") (pintype "passive"))
      (node (ref "POT_B") (pin "P$3") (pinfunction "A_P$3") (pintype "passive"))
      (node (ref "POT_C") (pin "P$3") (pinfunction "A_P$3") (pintype "passive"))
      (node (ref "Q1") (pin "2") (pinfunction "LID1_2") (pintype "power_in"))
      (node (ref "Q1") (pin "4") (pinfunction "LID2_4") (pintype "power_in"))
      (node (ref "Q2") (pin "E") (pinfunction "E_E") (pintype "passive"))
      (node (ref "Q3") (pin "E") (pinfunction "E_E") (pintype "passive"))
      (node (ref "Q4") (pin "E") (pinfunction "E_E") (pintype "passive"))
      (node (ref "R20") (pin "1") (pinfunction "1_1") (pintype "passive"))
      (node (ref "R21") (pin "1") (pinfunction "1_1") (pintype "passive"))
      (node (ref "R23") (pin "1") (pinfunction "1_1") (pintype "passive"))
      (node (ref "R45") (pin "2") (pinfunction "2_2") (pintype "passive"))
      (node (ref "R46") (pin "2") (pinfunction "2_2") (pintype "passive"))
      (node (ref "R47") (pin "2") (pinfunction "2_2") (pintype "passive"))
      (node (ref "R48") (pin "2") (pinfunction "2_2") (pintype "passive"))
      (node (ref "R49") (pin "2") (pinfunction "2_2") (pintype "passive"))
      (node (ref "R5") (pin "2") (pinfunction "2_2") (pintype "passive"))
      (node (ref "R50") (pin "2") (pinfunction "2_2") (pintype "passive"))
      (node (ref "SLD_A") (pin "1") (pinfunction "A_1") (pintype "passive"))
      (node (ref "SLD_B") (pin "1") (pinfunction "A_1") (pintype "passive"))
      (node (ref "SLD_C") (pin "1") (pinfunction "A_1") (pintype "passive"))
      (node (ref "SW_A") (pin "1") (pinfunction "1_1") (pintype "passive"))
      (node (ref "SW_A") (pin "2") (pinfunction "2_2") (pintype "passive"))
      (node (ref "SW_B") (pin "1") (pinfunction "1_1") (pintype "passive"))
      (node (ref "SW_B") (pin "2") (pinfunction "2_2") (pintype "passive"))
      (node (ref "SW_C") (pin "1") (pinfunction "1_1") (pintype "passive"))
      (node (ref "SW_C") (pin "2") (pinfunction "2_2") (pintype "passive"))
      (node (ref "U$1") (pin "6") (pinfunction "P$6_6") (pintype "bidirectional"))
      (node (ref "U1") (pin "16") (pinfunction "VSS_2_16") (pintype "power_in"))
      (node (ref "U1") (pin "31") (pinfunction "BOOT0_31") (pintype "input"))
      (node (ref "U1") (pin "32") (pinfunction "VSS_1_32") (pintype "power_in"))
      (node (ref "U2") (pin "10") (pinfunction "+IN_10") (pintype "input"))
      (node (ref "U2") (pin "11") (pinfunction "V-_11") (pintype "power_in"))
      (node (ref "U2") (pin "12") (pinfunction "+IN_12") (pintype "input"))
      (node (ref "U2") (pin "3") (pinfunction "+IN_3") (pintype "input"))
      (node (ref "U2") (pin "5") (pinfunction "+IN_5") (pintype "input"))
      (node (ref "U3") (pin "10") (pinfunction "+IN_10") (pintype "input"))
      (node (ref "U3") (pin "12") (pinfunction "+IN_12") (pintype "input"))
      (node (ref "U3") (pin "3") (pinfunction "+IN_3") (pintype "input"))
      (node (ref "U3") (pin "5") (pinfunction "+IN_5") (pintype "input"))
    )
    (net (code "25") (name "LEDS_SCK") (class "Default")
      (node (ref "IC5") (pin "3") (pinfunction "SCLK_3") (pintype "bidirectional"))
      (node (ref "U1") (pin "26") (pinfunction "PB3_26") (pintype "bidirectional"))
    )
    (net (code "26") (name "LEDS_SIN") (class "Default")
      (node (ref "IC5") (pin "2") (pinfunction "SIN_2") (pintype "bidirectional"))
      (node (ref "U1") (pin "28") (pinfunction "PB5_28") (pintype "bidirectional"))
    )
    (net (code "27") (name "LEDS_SS") (class "Default")
      (node (ref "IC5") (pin "4") (pinfunction "LAT_4") (pintype "bidirectional"))
      (node (ref "JP3") (pin "2") (pinfunction "2_2") (pintype "passive"))
    )
    (net (code "28") (name "N_U") (class "Default")
      (node (ref "U2") (pin "6") (pinfunction "-IN_6") (pintype "input"))
      (node (ref "U2") (pin "7") (pinfunction "OUT_7") (pintype "output"))
    )
    (net (code "29") (name "Net-(A-GRN)") (class "Default")
      (node (ref "A") (pin "GREEN_C") (pinfunction "GRN_GREEN_C") (pintype "bidirectional"))
      (node (ref "IC5") (pin "11") (pinfunction "OUT6_11") (pintype "bidirectional"))
    )
    (net (code "30") (name "Net-(A-RED)") (class "Default")
      (node (ref "A") (pin "RED_C") (pinfunction "RED_RED_C") (pintype "bidirectional"))
      (node (ref "IC5") (pin "10") (pinfunction "OUT5_10") (pintype "bidirectional"))
    )
    (net (code "31") (name "Net-(B-GRN)") (class "Default")
      (node (ref "B") (pin "GREEN_C") (pinfunction "GRN_GREEN_C") (pintype "bidirectional"))
      (node (ref "IC5") (pin "9") (pinfunction "OUT4_9") (pintype "bidirectional"))
    )
    (net (code "32") (name "Net-(B-RED)") (class "Default")
      (node (ref "B") (pin "RED_C") (pinfunction "RED_RED_C") (pintype "bidirectional"))
      (node (ref "IC5") (pin "8") (pinfunction "OUT3_8") (pintype "bidirectional"))
    )
    (net (code "33") (name "Net-(C-GRN)") (class "Default")
      (node (ref "C") (pin "GREEN_C") (pinfunction "GRN_GREEN_C") (pintype "bidirectional"))
      (node (ref "IC5") (pin "7") (pinfunction "OUT2_7") (pintype "bidirectional"))
    )
    (net (code "34") (name "Net-(C-RED)") (class "Default")
      (node (ref "C") (pin "RED_C") (pinfunction "RED_RED_C") (pintype "bidirectional"))
      (node (ref "IC5") (pin "6") (pinfunction "OUT1_6") (pintype "bidirectional"))
    )
    (net (code "35") (name "Net-(C1-Pad1)") (class "Default")
      (node (ref "C1") (pin "1") (pinfunction "1_1") (pintype "passive"))
      (node (ref "D1") (pin "C") (pinfunction "C_C") (pintype "passive"))
      (node (ref "L1") (pin "1") (pinfunction "1_1") (pintype "passive"))
      (node (ref "L2") (pin "2") (pinfunction "2_2") (pintype "passive"))
      (node (ref "L3") (pin "2") (pinfunction "2_2") (pintype "passive"))
    )
    (net (code "36") (name "Net-(C3-Pad1)") (class "Default")
      (node (ref "C3") (pin "1") (pinfunction "1_1") (pintype "passive"))
      (node (ref "IC2") (pin "2") (pinfunction "IN_2") (pintype "input"))
      (node (ref "IC2") (pin "4") (pinfunction "IN_4") (pintype "input"))
      (node (ref "L2") (pin "1") (pinfunction "1_1") (pintype "passive"))
    )
    (net (code "37") (name "Net-(C22-Pad2)") (class "Default")
      (node (ref "C22") (pin "2") (pinfunction "2_2") (pintype "passive"))
      (node (ref "Q1") (pin "1") (pinfunction "1_1") (pintype "passive"))
      (node (ref "R6") (pin "2") (pinfunction "2_2") (pintype "passive"))
    )
    (net (code "38") (name "Net-(D2-PadA)") (class "Default")
      (node (ref "D2") (pin "A") (pinfunction "A_A") (pintype "passive"))
      (node (ref "L4") (pin "2") (pinfunction "2_2") (pintype "passive"))
    )
    (net (code "39") (name "Net-(D3-PadC)") (class "Default")
      (node (ref "D3") (pin "C") (pinfunction "C_C") (pintype "passive"))
      (node (ref "Q2") (pin "B") (pinfunction "B_B") (pintype "passive"))
      (node (ref "R18") (pin "2") (pinfunction "2_2") (pintype "passive"))
      (node (ref "R23") (pin "2") (pinfunction "2_2") (pintype "passive"))
    )
    (net (code "40") (name "Net-(D4-PadC)") (class "Default")
      (node (ref "D4") (pin "C") (pinfunction "C_C") (pintype "passive"))
      (node (ref "Q3") (pin "B") (pinfunction "B_B") (pintype "passive"))
      (node (ref "R19") (pin "2") (pinfunction "2_2") (pintype "passive"))
      (node (ref "R20") (pin "2") (pinfunction "2_2") (pintype "passive"))
    )
    (net (code "41") (name "Net-(D5-PadC)") (class "Default")
      (node (ref "D5") (pin "C") (pinfunction "C_C") (pintype "passive"))
      (node (ref "Q4") (pin "B") (pinfunction "B_B") (pintype "passive"))
      (node (ref "R21") (pin "2") (pinfunction "2_2") (pintype "passive"))
      (node (ref "R22") (pin "2") (pinfunction "2_2") (pintype "passive"))
    )
    (net (code "42") (name "Net-(IC1-VI)") (class "Default")
      (node (ref "C5") (pin "1") (pinfunction "1_1") (pintype "passive"))
      (node (ref "IC1") (pin "1") (pinfunction "VI_1") (pintype "input"))
      (node (ref "L1") (pin "2") (pinfunction "2_2") (pintype "passive"))
    )
    (net (code "43") (name "Net-(IC4A-X0)") (class "Default")
      (node (ref "IC4") (pin "13") (pinfunction "X0_13") (pintype "bidirectional"))
      (node (ref "POT_C") (pin "P$2") (pinfunction "S_P$2") (pintype "passive"))
    )
    (net (code "44") (name "Net-(IC4A-X1)") (class "Default")
      (node (ref "IC4") (pin "14") (pinfunction "X1_14") (pintype "bidirectional"))
      (node (ref "SLD_C") (pin "2") (pinfunction "S_2") (pintype "passive"))
    )
    (net (code "45") (name "Net-(IC4A-X2)") (class "Default")
      (node (ref "IC4") (pin "15") (pinfunction "X2_15") (pintype "bidirectional"))
      (node (ref "SLD_B") (pin "2") (pinfunction "S_2") (pintype "passive"))
    )
    (net (code "46") (name "Net-(IC4A-X3)") (class "Default")
      (node (ref "IC4") (pin "12") (pinfunction "X3_12") (pintype "bidirectional"))
      (node (ref "POT_A") (pin "P$2") (pinfunction "S_P$2") (pintype "passive"))
    )
    (net (code "47") (name "Net-(IC4A-X4)") (class "Default")
      (node (ref "IC4") (pin "1") (pinfunction "X4_1") (pintype "bidirectional"))
      (node (ref "SLD_A") (pin "2") (pinfunction "S_2") (pintype "passive"))
    )
    (net (code "48") (name "Net-(IC4A-X5)") (class "Default")
      (node (ref "IC4") (pin "5") (pinfunction "X5_5") (pintype "bidirectional"))
      (node (ref "POT_B") (pin "P$2") (pinfunction "S_P$2") (pintype "passive"))
    )
    (net (code "49") (name "Net-(IC5-IREF)") (class "Default")
      (node (ref "IC5") (pin "23") (pinfunction "IREF_23") (pintype "bidirectional"))
      (node (ref "R5") (pin "1") (pinfunction "1_1") (pintype "passive"))
    )
    (net (code "50") (name "Net-(IC5-OUT7)") (class "Default")
      (node (ref "IC5") (pin "12") (pinfunction "OUT7_12") (pintype "bidirectional"))
      (node (ref "R16") (pin "2") (pinfunction "2_2") (pintype "passive"))
    )
    (net (code "51") (name "Net-(IC5-OUT8)") (class "Default")
      (node (ref "IC5") (pin "13") (pinfunction "OUT8_13") (pintype "bidirectional"))
      (node (ref "R17") (pin "2") (pinfunction "2_2") (pintype "passive"))
    )
    (net (code "52") (name "Net-(IC5-OUT9)") (class "Default")
      (node (ref "IC5") (pin "14") (pinfunction "OUT9_14") (pintype "bidirectional"))
      (node (ref "R15") (pin "2") (pinfunction "2_2") (pintype "passive"))
    )
    (net (code "53") (name "Net-(IC5-VCC)") (class "Default")
      (node (ref "C14") (pin "1") (pinfunction "1_1") (pintype "passive"))
      (node (ref "C15") (pin "1") (pinfunction "1_1") (pintype "passive"))
      (node (ref "IC5") (pin "24") (pinfunction "VCC_24") (pintype "bidirectional"))
      (node (ref "L5") (pin "1") (pinfunction "1_1") (pintype "passive"))
    )
    (net (code "54") (name "Net-(IC6A-+IN)") (class "Default")
      (node (ref "IC6") (pin "3") (pinfunction "+IN_3") (pintype "input"))
      (node (ref "R44") (pin "2") (pinfunction "2_2") (pintype "passive"))
      (node (ref "R47") (pin "1") (pinfunction "1_1") (pintype "passive"))
    )
    (net (code "55") (name "Net-(IC6A--IN)") (class "Default")
      (node (ref "IC6") (pin "2") (pinfunction "-IN_2") (pintype "input"))
      (node (ref "R13") (pin "1") (pinfunction "1_1") (pintype "passive"))
    )
    (net (code "56") (name "Net-(IC6A-OUT)") (class "Default")
      (node (ref "IC6") (pin "1") (pinfunction "OUT_1") (pintype "output"))
      (node (ref "R39") (pin "2") (pinfunction "2_2") (pintype "passive"))
      (node (ref "R44") (pin "1") (pinfunction "1_1") (pintype "passive"))
    )
    (net (code "57") (name "Net-(IC6B-+IN)") (class "Default")
      (node (ref "IC6") (pin "5") (pinfunction "+IN_5") (pintype "input"))
      (node (ref "R41") (pin "2") (pinfunction "2_2") (pintype "passive"))
      (node (ref "R46") (pin "1") (pinfunction "1_1") (pintype "passive"))
    )
    (net (code "58") (name "Net-(IC6B--IN)") (class "Default")
      (node (ref "IC6") (pin "6") (pinfunction "-IN_6") (pintype "input"))
      (node (ref "R12") (pin "1") (pinfunction "1_1") (pintype "passive"))
    )
    (net (code "59") (name "Net-(IC6B-OUT)") (class "Default")
      (node (ref "IC6") (pin "7") (pinfunction "OUT_7") (pintype "output"))
      (node (ref "R38") (pin "2") (pinfunction "2_2") (pintype "passive"))
      (node (ref "R41") (pin "1") (pinfunction "1_1") (pintype "passive"))
    )
    (net (code "60") (name "Net-(IC6C-+IN)") (class "Default")
      (node (ref "IC6") (pin "10") (pinfunction "+IN_10") (pintype "input"))
      (node (ref "R36") (pin "2") (pinfunction "2_2") (pintype "passive"))
      (node (ref "R45") (pin "1") (pinfunction "1_1") (pintype "passive"))
    )
    (net (code "61") (name "Net-(IC6C--IN)") (class "Default")
      (node (ref "IC6") (pin "9") (pinfunction "-IN_9") (pintype "input"))
      (node (ref "R11") (pin "1") (pinfunction "1_1") (pintype "passive"))
    )
    (net (code "62") (name "Net-(IC6C-OUT)") (class "Default")
      (node (ref "IC6") (pin "8") (pinfunction "OUT_8") (pintype "output"))
      (node (ref "R36") (pin "1") (pinfunction "1_1") (pintype "passive"))
      (node (ref "R37") (pin "2") (pinfunction "2_2") (pintype "passive"))
    )
    (net (code "63") (name "Net-(IC6D--IN)") (class "Default")
      (node (ref "IC6") (pin "13") (pinfunction "-IN_13") (pintype "input"))
      (node (ref "IC6") (pin "14") (pinfunction "OUT_14") (pintype "output"))
    )
    (net (code "64") (name "Net-(IC14A-+IN)") (class "Default")
      (node (ref "IC14") (pin "3") (pinfunction "+IN_3") (pintype "input"))
      (node (ref "LED3") (pin "2") (pinfunction "2_2") (pintype "bidirectional"))
      (node (ref "R48") (pin "1") (pinfunction "1_1") (pintype "passive"))
    )
    (net (code "65") (name "Net-(IC14A--IN)") (class "Default")
      (node (ref "C33") (pin "2") (pinfunction "2_2") (pintype "passive"))
      (node (ref "IC14") (pin "2") (pinfunction "-IN_2") (pintype "input"))
      (node (ref "R43") (pin "2") (pinfunction "2_2") (pintype "passive"))
      (node (ref "U3") (pin "1") (pinfunction "OUT_1") (pintype "output"))
    )
    (net (code "66") (name "Net-(IC14A-OUT)") (class "Default")
      (node (ref "IC14") (pin "1") (pinfunction "OUT_1") (pintype "output"))
      (node (ref "LED3") (pin "1") (pinfunction "1_1") (pintype "bidirectional"))
    )
    (net (code "67") (name "Net-(IC14B-+IN)") (class "Default")
      (node (ref "C32") (pin "2") (pinfunction "2_2") (pintype "passive"))
      (node (ref "IC14") (pin "5") (pinfunction "+IN_5") (pintype "input"))
      (node (ref "R42") (pin "2") (pinfunction "2_2") (pintype "passive"))
      (node (ref "U3") (pin "7") (pinfunction "OUT_7") (pintype "output"))
    )
    (net (code "68") (name "Net-(IC14B--IN)") (class "Default")
      (node (ref "IC14") (pin "6") (pinfunction "-IN_6") (pintype "input"))
      (node (ref "LED1") (pin "2") (pinfunction "2_2") (pintype "bidirectional"))
      (node (ref "R49") (pin "1") (pinfunction "1_1") (pintype "passive"))
    )
    (net (code "69") (name "Net-(IC14B-OUT)") (class "Default")
      (node (ref "IC14") (pin "7") (pinfunction "OUT_7") (pintype "output"))
      (node (ref "LED1") (pin "1") (pinfunction "1_1") (pintype "bidirectional"))
    )
    (net (code "70") (name "Net-(IC14C-+IN)") (class "Default")
      (node (ref "IC14") (pin "10") (pinfunction "+IN_10") (pintype "input"))
      (node (ref "LED2") (pin "2") (pinfunction "2_2") (pintype "bidirectional"))
      (node (ref "R50") (pin "1") (pinfunction "1_1") (pintype "passive"))
    )
    (net (code "71") (name "Net-(IC14C--IN)") (class "Default")
      (node (ref "C34") (pin "2") (pinfunction "2_2") (pintype "passive"))
      (node (ref "IC14") (pin "9") (pinfunction "-IN_9") (pintype "input"))
      (node (ref "R40") (pin "2") (pinfunction "2_2") (pintype "passive"))
      (node (ref "U3") (pin "8") (pinfunction "OUT_8") (pintype "output"))
    )
    (net (code "72") (name "Net-(IC14C-OUT)") (class "Default")
      (node (ref "IC14") (pin "8") (pinfunction "OUT_8") (pintype "output"))
      (node (ref "LED2") (pin "1") (pinfunction "1_1") (pintype "bidirectional"))
    )
    (net (code "73") (name "Net-(IC14D-+IN)") (class "Default")
      (node (ref "IC14") (pin "12") (pinfunction "+IN_12") (pintype "input"))
      (node (ref "IC14") (pin "14") (pinfunction "OUT_14") (pintype "output"))
    )
    (net (code "74") (name "Net-(J4-3)") (class "Default")
      (node (ref "J4") (pin "P3") (pinfunction "3_P3") (pintype "passive"))
      (node (ref "R24") (pin "2") (pinfunction "2_2") (pintype "passive"))
    )
    (net (code "75") (name "Net-(J6-3)") (class "Default")
      (node (ref "J6") (pin "P3") (pinfunction "3_P3") (pintype "passive"))
      (node (ref "R26") (pin "2") (pinfunction "2_2") (pintype "passive"))
    )
    (net (code "76") (name "Net-(J7-3)") (class "Default")
      (node (ref "J7") (pin "P3") (pinfunction "3_P3") (pintype "passive"))
      (node (ref "R37") (pin "1") (pinfunction "1_1") (pintype "passive"))
    )
    (net (code "77") (name "Net-(J8-3)") (class "Default")
      (node (ref "J8") (pin "P3") (pinfunction "3_P3") (pintype "passive"))
      (node (ref "R38") (pin "1") (pinfunction "1_1") (pintype "passive"))
    )
    (net (code "78") (name "Net-(J9-3)") (class "Default")
      (node (ref "J9") (pin "P3") (pinfunction "3_P3") (pintype "passive"))
      (node (ref "R39") (pin "1") (pinfunction "1_1") (pintype "passive"))
    )
    (net (code "79") (name "Net-(J10-3)") (class "Default")
      (node (ref "J10") (pin "P3") (pinfunction "3_P3") (pintype "passive"))
      (node (ref "R35") (pin "1") (pinfunction "1_1") (pintype "passive"))
      (node (ref "R40") (pin "1") (pinfunction "1_1") (pintype "passive"))
    )
    (net (code "80") (name "Net-(J11-3)") (class "Default")
      (node (ref "J11") (pin "P3") (pinfunction "3_P3") (pintype "passive"))
      (node (ref "R29") (pin "1") (pinfunction "1_1") (pintype "passive"))
      (node (ref "R42") (pin "1") (pinfunction "1_1") (pintype "passive"))
    )
    (net (code "81") (name "Net-(J12-3)") (class "Default")
      (node (ref "J12") (pin "P3") (pinfunction "3_P3") (pintype "passive"))
      (node (ref "R32") (pin "1") (pinfunction "1_1") (pintype "passive"))
      (node (ref "R43") (pin "1") (pinfunction "1_1") (pintype "passive"))
    )
    (net (code "82") (name "Net-(Q1B-2)") (class "Default")
      (node (ref "C21") (pin "2") (pinfunction "2_2") (pintype "passive"))
      (node (ref "Q1") (pin "3") (pinfunction "2_3") (pintype "passive"))
      (node (ref "R9") (pin "2") (pinfunction "2_2") (pintype "passive"))
    )
    (net (code "83") (name "Net-(SLD_AA-A)") (class "Default")
      (node (ref "SLD_A") (pin "B") (pinfunction "A_B") (pintype "passive"))
      (node (ref "SLD_B") (pin "B") (pinfunction "A_B") (pintype "passive"))
      (node (ref "SLD_C") (pin "B") (pinfunction "A_B") (pintype "passive"))
    )
    (net (code "84") (name "Net-(SLD_AA-C)") (class "Default")
      (node (ref "R16") (pin "1") (pinfunction "1_1") (pintype "passive"))
      (node (ref "SLD_A") (pin "E") (pinfunction "C_E") (pintype "passive"))
    )
    (net (code "85") (name "Net-(SLD_BA-C)") (class "Default")
      (node (ref "R17") (pin "1") (pinfunction "1_1") (pintype "passive"))
      (node (ref "SLD_B") (pin "E") (pinfunction "C_E") (pintype "passive"))
    )
    (net (code "86") (name "Net-(SLD_CA-C)") (class "Default")
      (node (ref "R15") (pin "1") (pinfunction "1_1") (pintype "passive"))
      (node (ref "SLD_C") (pin "E") (pinfunction "C_E") (pintype "passive"))
    )
    (net (code "87") (name "Net-(U1-PF0{slash}OSC_IN)") (class "Default")
      (node (ref "R9") (pin "1") (pinfunction "1_1") (pintype "passive"))
      (node (ref "U1") (pin "2") (pinfunction "PF0/OSC_IN_2") (pintype "bidirectional"))
    )
    (net (code "88") (name "Net-(U1-PF1{slash}OSC_OUT)") (class "Default")
      (node (ref "R6") (pin "1") (pinfunction "1_1") (pintype "passive"))
      (node (ref "U1") (pin "3") (pinfunction "PF1/OSC_OUT_3") (pintype "bidirectional"))
    )
    (net (code "89") (name "Net-(U2A--IN)") (class "Default")
      (node (ref "C30") (pin "1") (pinfunction "1_1") (pintype "passive"))
      (node (ref "R14") (pin "2") (pinfunction "2_2") (pintype "passive"))
      (node (ref "R2") (pin "1") (pinfunction "1_1") (pintype "passive"))
      (node (ref "R26") (pin "1") (pinfunction "1_1") (pintype "passive"))
      (node (ref "U2") (pin "2") (pinfunction "-IN_2") (pintype "input"))
    )
    (net (code "90") (name "Net-(U2C--IN)") (class "Default")
      (node (ref "C23") (pin "1") (pinfunction "1_1") (pintype "passive"))
      (node (ref "R25") (pin "1") (pinfunction "1_1") (pintype "passive"))
      (node (ref "R3") (pin "1") (pinfunction "1_1") (pintype "passive"))
      (node (ref "R7") (pin "2") (pinfunction "2_2") (pintype "passive"))
      (node (ref "U2") (pin "9") (pinfunction "-IN_9") (pintype "input"))
    )
    (net (code "91") (name "Net-(U2D--IN)") (class "Default")
      (node (ref "C24") (pin "1") (pinfunction "1_1") (pintype "passive"))
      (node (ref "R24") (pin "1") (pinfunction "1_1") (pintype "passive"))
      (node (ref "R4") (pin "1") (pinfunction "1_1") (pintype "passive"))
      (node (ref "R8") (pin "2") (pinfunction "2_2") (pintype "passive"))
      (node (ref "U2") (pin "13") (pinfunction "-IN_13") (pintype "input"))
    )
    (net (code "92") (name "Net-(U3A--IN)") (class "Default")
      (node (ref "C33") (pin "1") (pinfunction "1_1") (pintype "passive"))
      (node (ref "R30") (pin "1") (pinfunction "1_1") (pintype "passive"))
      (node (ref "R31") (pin "1") (pinfunction "1_1") (pintype "passive"))
      (node (ref "R32") (pin "2") (pinfunction "2_2") (pintype "passive"))
      (node (ref "U3") (pin "2") (pinfunction "-IN_2") (pintype "input"))
    )
    (net (code "93") (name "Net-(U3B--IN)") (class "Default")
      (node (ref "C32") (pin "1") (pinfunction "1_1") (pintype "passive"))
      (node (ref "R27") (pin "1") (pinfunction "1_1") (pintype "passive"))
      (node (ref "R28") (pin "1") (pinfunction "1_1") (pintype "passive"))
      (node (ref "R29") (pin "2") (pinfunction "2_2") (pintype "passive"))
      (node (ref "U3") (pin "6") (pinfunction "-IN_6") (pintype "input"))
    )
    (net (code "94") (name "Net-(U3C--IN)") (class "Default")
      (node (ref "C34") (pin "1") (pinfunction "1_1") (pintype "passive"))
      (node (ref "R33") (pin "1") (pinfunction "1_1") (pintype "passive"))
      (node (ref "R34") (pin "1") (pinfunction "1_1") (pintype "passive"))
      (node (ref "R35") (pin "2") (pinfunction "2_2") (pintype "passive"))
      (node (ref "U3") (pin "9") (pinfunction "-IN_9") (pintype "input"))
    )
    (net (code "95") (name "Net-(U3D--IN)") (class "Default")
      (node (ref "U3") (pin "13") (pinfunction "-IN_13") (pintype "input"))
      (node (ref "U3") (pin "14") (pinfunction "OUT_14") (pintype "output"))
    )
    (net (code "96") (name "POTS_ADDR_A") (class "Default")
      (node (ref "IC4") (pin "11") (pinfunction "A_11") (pintype "input"))
      (node (ref "U1") (pin "13") (pinfunction "PA7_13") (pintype "bidirectional"))
    )
    (net (code "97") (name "POTS_ADDR_B") (class "Default")
      (node (ref "IC4") (pin "10") (pinfunction "B_10") (pintype "input"))
      (node (ref "U1") (pin "18") (pinfunction "PA8_18") (pintype "bidirectional"))
    )
    (net (code "98") (name "POTS_ADDR_C") (class "Default")
      (node (ref "IC4") (pin "9") (pinfunction "C_9") (pintype "input"))
      (node (ref "U1") (pin "19") (pinfunction "PA9_19") (pintype "bidirectional"))
    )
    (net (code "99") (name "RESET") (class "Default")
      (node (ref "C28") (pin "1") (pinfunction "1_1") (pintype "passive"))
      (node (ref "JP2") (pin "4") (pinfunction "4_4") (pintype "passive"))
      (node (ref "R10") (pin "2") (pinfunction "2_2") (pintype "passive"))
      (node (ref "U1") (pin "4") (pinfunction "NRST_4") (pintype "bidirectional"))
    )
    (net (code "100") (name "SWCLK") (class "Default")
      (node (ref "JP2") (pin "3") (pinfunction "3_3") (pintype "passive"))
      (node (ref "U1") (pin "24") (pinfunction "PA14_24") (pintype "bidirectional"))
    )
    (net (code "101") (name "SWDIO_SS") (class "Default")
      (node (ref "JP2") (pin "2") (pinfunction "2_2") (pintype "passive"))
      (node (ref "JP3") (pin "1") (pinfunction "1_1") (pintype "passive"))
      (node (ref "U1") (pin "23") (pinfunction "PA13_23") (pintype "bidirectional"))
    )
    (net (code "102") (name "SW_MODE_A") (class "Default")
      (node (ref "SW_A") (pin "3") (pinfunction "3_3") (pintype "passive"))
      (node (ref "SW_A") (pin "4") (pinfunction "4_4") (pintype "passive"))
      (node (ref "U1") (pin "27") (pinfunction "PB4_27") (pintype "bidirectional"))
    )
    (net (code "103") (name "SW_MODE_B") (class "Default")
      (node (ref "SW_B") (pin "3") (pinfunction "3_3") (pintype "passive"))
      (node (ref "SW_B") (pin "4") (pinfunction "4_4") (pintype "passive"))
      (node (ref "U1") (pin "29") (pinfunction "PB6_29") (pintype "bidirectional"))
    )
    (net (code "104") (name "SW_MODE_C") (class "Default")
      (node (ref "SW_C") (pin "3") (pinfunction "3_3") (pintype "passive"))
      (node (ref "SW_C") (pin "4") (pinfunction "4_4") (pintype "passive"))
      (node (ref "U1") (pin "30") (pinfunction "PB7_30") (pintype "bidirectional"))
    )
    (net (code "105") (name "VCC") (class "Default")
      (node (ref "C2") (pin "1") (pinfunction "1_1") (pintype "passive"))
      (node (ref "C31") (pin "1") (pinfunction "1_1") (pintype "passive"))
      (node (ref "C35") (pin "1") (pinfunction "1_1") (pintype "passive"))
      (node (ref "C36") (pin "1") (pinfunction "1_1") (pintype "passive"))
      (node (ref "C4") (pin "1") (pinfunction "1_1") (pintype "passive"))
      (node (ref "IC14") (pin "4") (pinfunction "V+_4") (pintype "power_in"))
      (node (ref "IC6") (pin "4") (pinfunction "V+_4") (pintype "power_in"))
      (node (ref "L3") (pin "1") (pinfunction "1_1") (pintype "passive"))
      (node (ref "U$1") (pin "1") (pinfunction "P$1_1") (pintype "bidirectional"))
      (node (ref "U3") (pin "4") (pinfunction "V+_4") (pintype "power_in"))
    )
    (net (code "106") (name "VEE") (class "Default")
      (node (ref "C10") (pin "2") (pinfunction "2_2") (pintype "passive"))
      (node (ref "C25") (pin "2") (pinfunction "2_2") (pintype "passive"))
      (node (ref "C37") (pin "2") (pinfunction "2_2") (pintype "passive"))
      (node (ref "C9") (pin "2") (pinfunction "2_2") (pintype "passive"))
      (node (ref "IC14") (pin "11") (pinfunction "V-_11") (pintype "power_in"))
      (node (ref "L4") (pin "1") (pinfunction "1_1") (pintype "passive"))
      (node (ref "R1") (pin "1") (pinfunction "1_1") (pintype "passive"))
      (node (ref "U$1") (pin "2") (pinfunction "P$2_2") (pintype "bidirectional"))
      (node (ref "U3") (pin "11") (pinfunction "V-_11") (pintype "power_in"))
    )
    (net (code "107") (name "unconnected-(IC4A-X7-Pad4)") (class "Default")
      (node (ref "IC4") (pin "4") (pinfunction "X7_4") (pintype "bidirectional"))
    )
    (net (code "108") (name "unconnected-(IC5-OUT0-Pad5)") (class "Default")
      (node (ref "IC5") (pin "5") (pinfunction "OUT0_5") (pintype "bidirectional"))
    )
    (net (code "109") (name "unconnected-(IC5-OUT10-Pad15)") (class "Default")
      (node (ref "IC5") (pin "15") (pinfunction "OUT10_15") (pintype "bidirectional"))
    )
    (net (code "110") (name "unconnected-(IC5-OUT11-Pad16)") (class "Default")
      (node (ref "IC5") (pin "16") (pinfunction "OUT11_16") (pintype "bidirectional"))
    )
    (net (code "111") (name "unconnected-(IC5-OUT12-Pad17)") (class "Default")
      (node (ref "IC5") (pin "17") (pinfunction "OUT12_17") (pintype "bidirectional"))
    )
    (net (code "112") (name "unconnected-(IC5-OUT13-Pad18)") (class "Default")
      (node (ref "IC5") (pin "18") (pinfunction "OUT13_18") (pintype "bidirectional"))
    )
    (net (code "113") (name "unconnected-(IC5-OUT14-Pad19)") (class "Default")
      (node (ref "IC5") (pin "19") (pinfunction "OUT14_19") (pintype "bidirectional"))
    )
    (net (code "114") (name "unconnected-(IC5-OUT15-Pad20)") (class "Default")
      (node (ref "IC5") (pin "20") (pinfunction "OUT15_20") (pintype "bidirectional"))
    )
    (net (code "115") (name "unconnected-(IC5-SOUT-Pad22)") (class "Default")
      (node (ref "IC5") (pin "22") (pinfunction "SOUT_22") (pintype "bidirectional"))
    )
    (net (code "116") (name "unconnected-(J7-2-PadP2)") (class "Default")
      (node (ref "J7") (pin "P2") (pinfunction "2_P2") (pintype "passive"))
    )
    (net (code "117") (name "unconnected-(J8-2-PadP2)") (class "Default")
      (node (ref "J8") (pin "P2") (pinfunction "2_P2") (pintype "passive"))
    )
    (net (code "118") (name "unconnected-(J9-2-PadP2)") (class "Default")
      (node (ref "J9") (pin "P2") (pinfunction "2_P2") (pintype "passive"))
    )
    (net (code "119") (name "unconnected-(J10-2-PadP2)") (class "Default")
      (node (ref "J10") (pin "P2") (pinfunction "2_P2") (pintype "passive"))
    )
    (net (code "120") (name "unconnected-(J11-2-PadP2)") (class "Default")
      (node (ref "J11") (pin "P2") (pinfunction "2_P2") (pintype "passive"))
    )
    (net (code "121") (name "unconnected-(J12-2-PadP2)") (class "Default")
      (node (ref "J12") (pin "P2") (pinfunction "2_P2") (pintype "passive"))
    )
  )
)
